# MotorPR.net
KiCad netlist of a schematic drawn in EAGLE
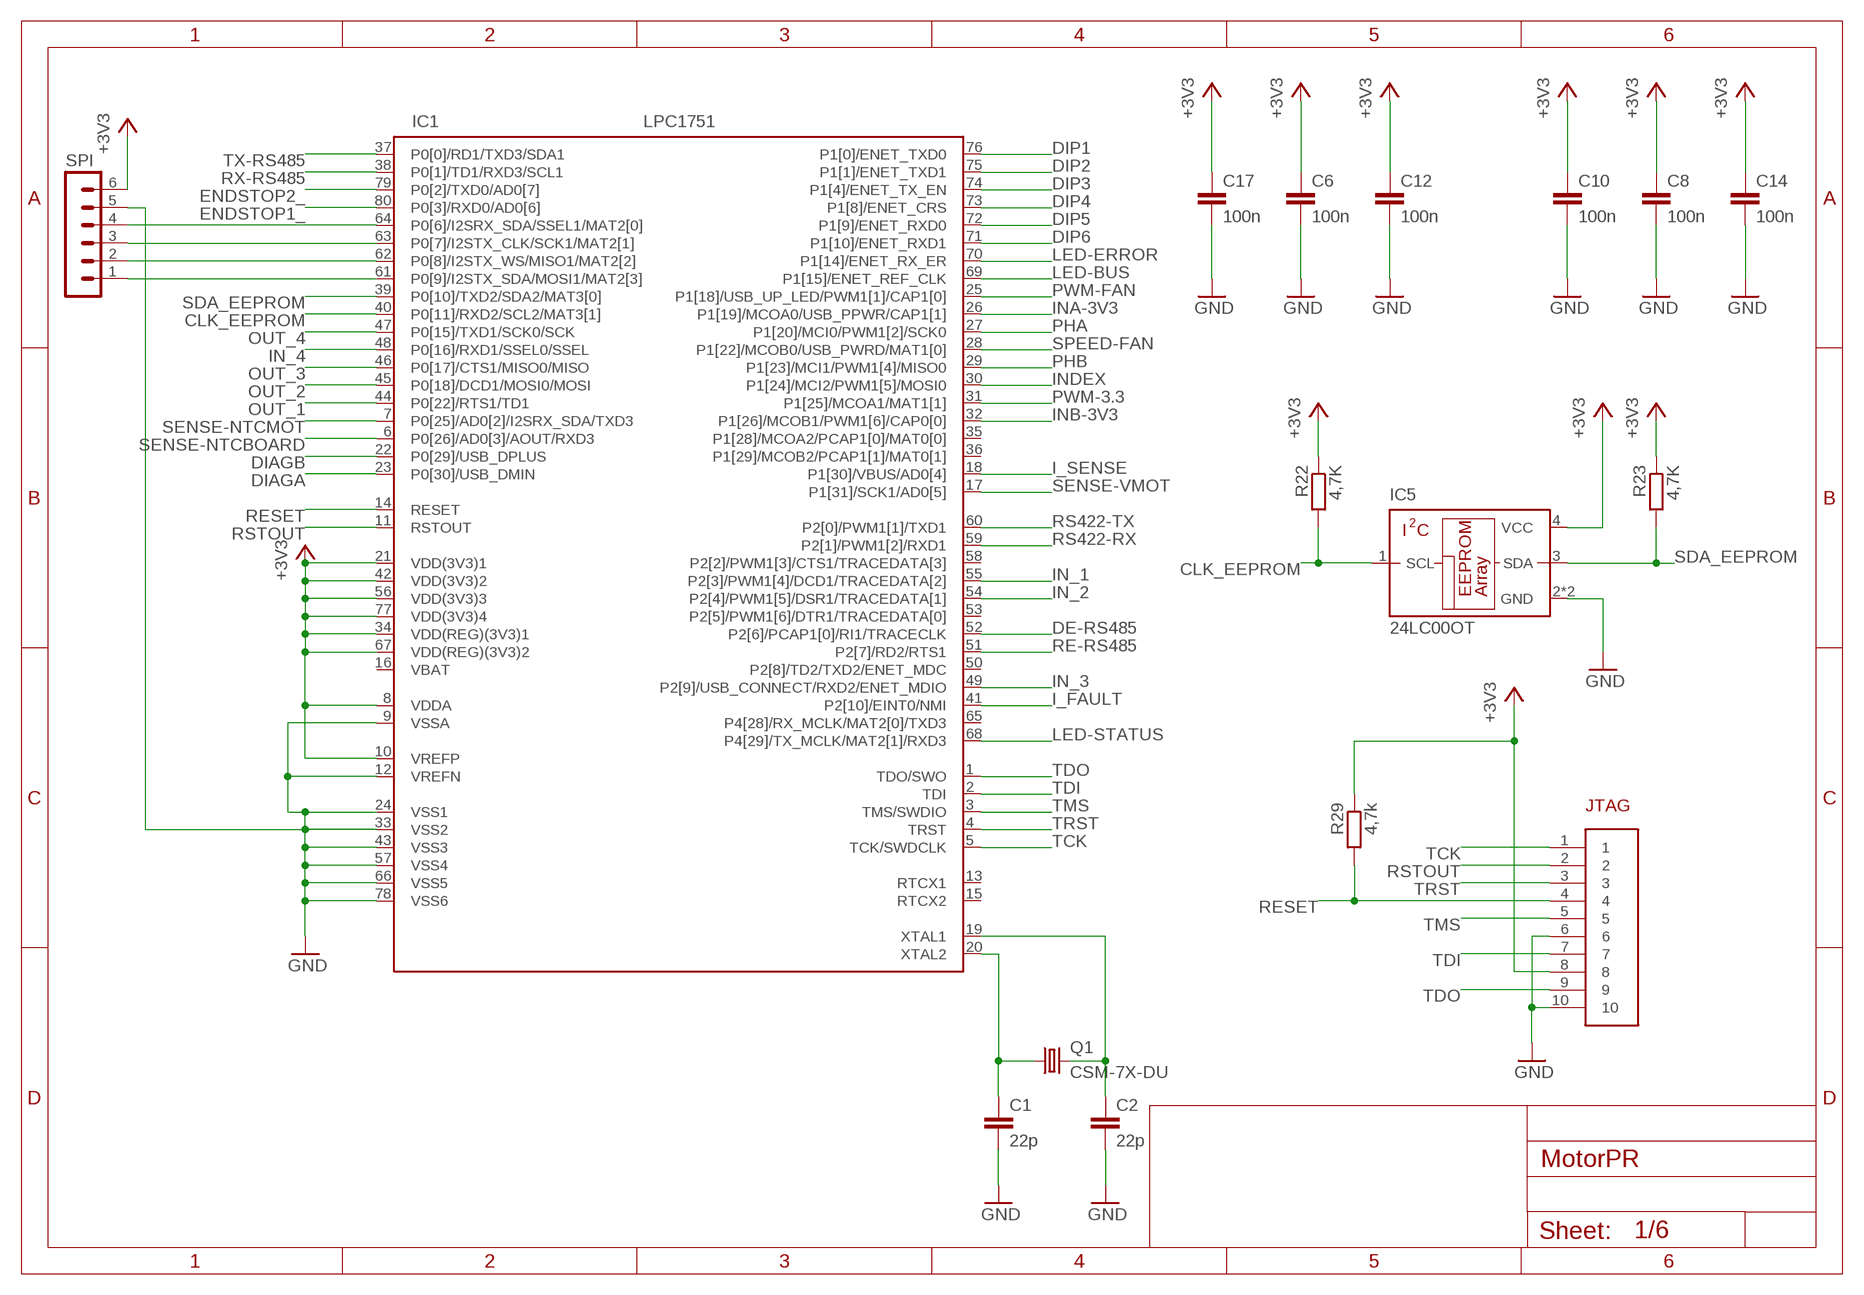
[diagram p0: schematic, sheet 1]
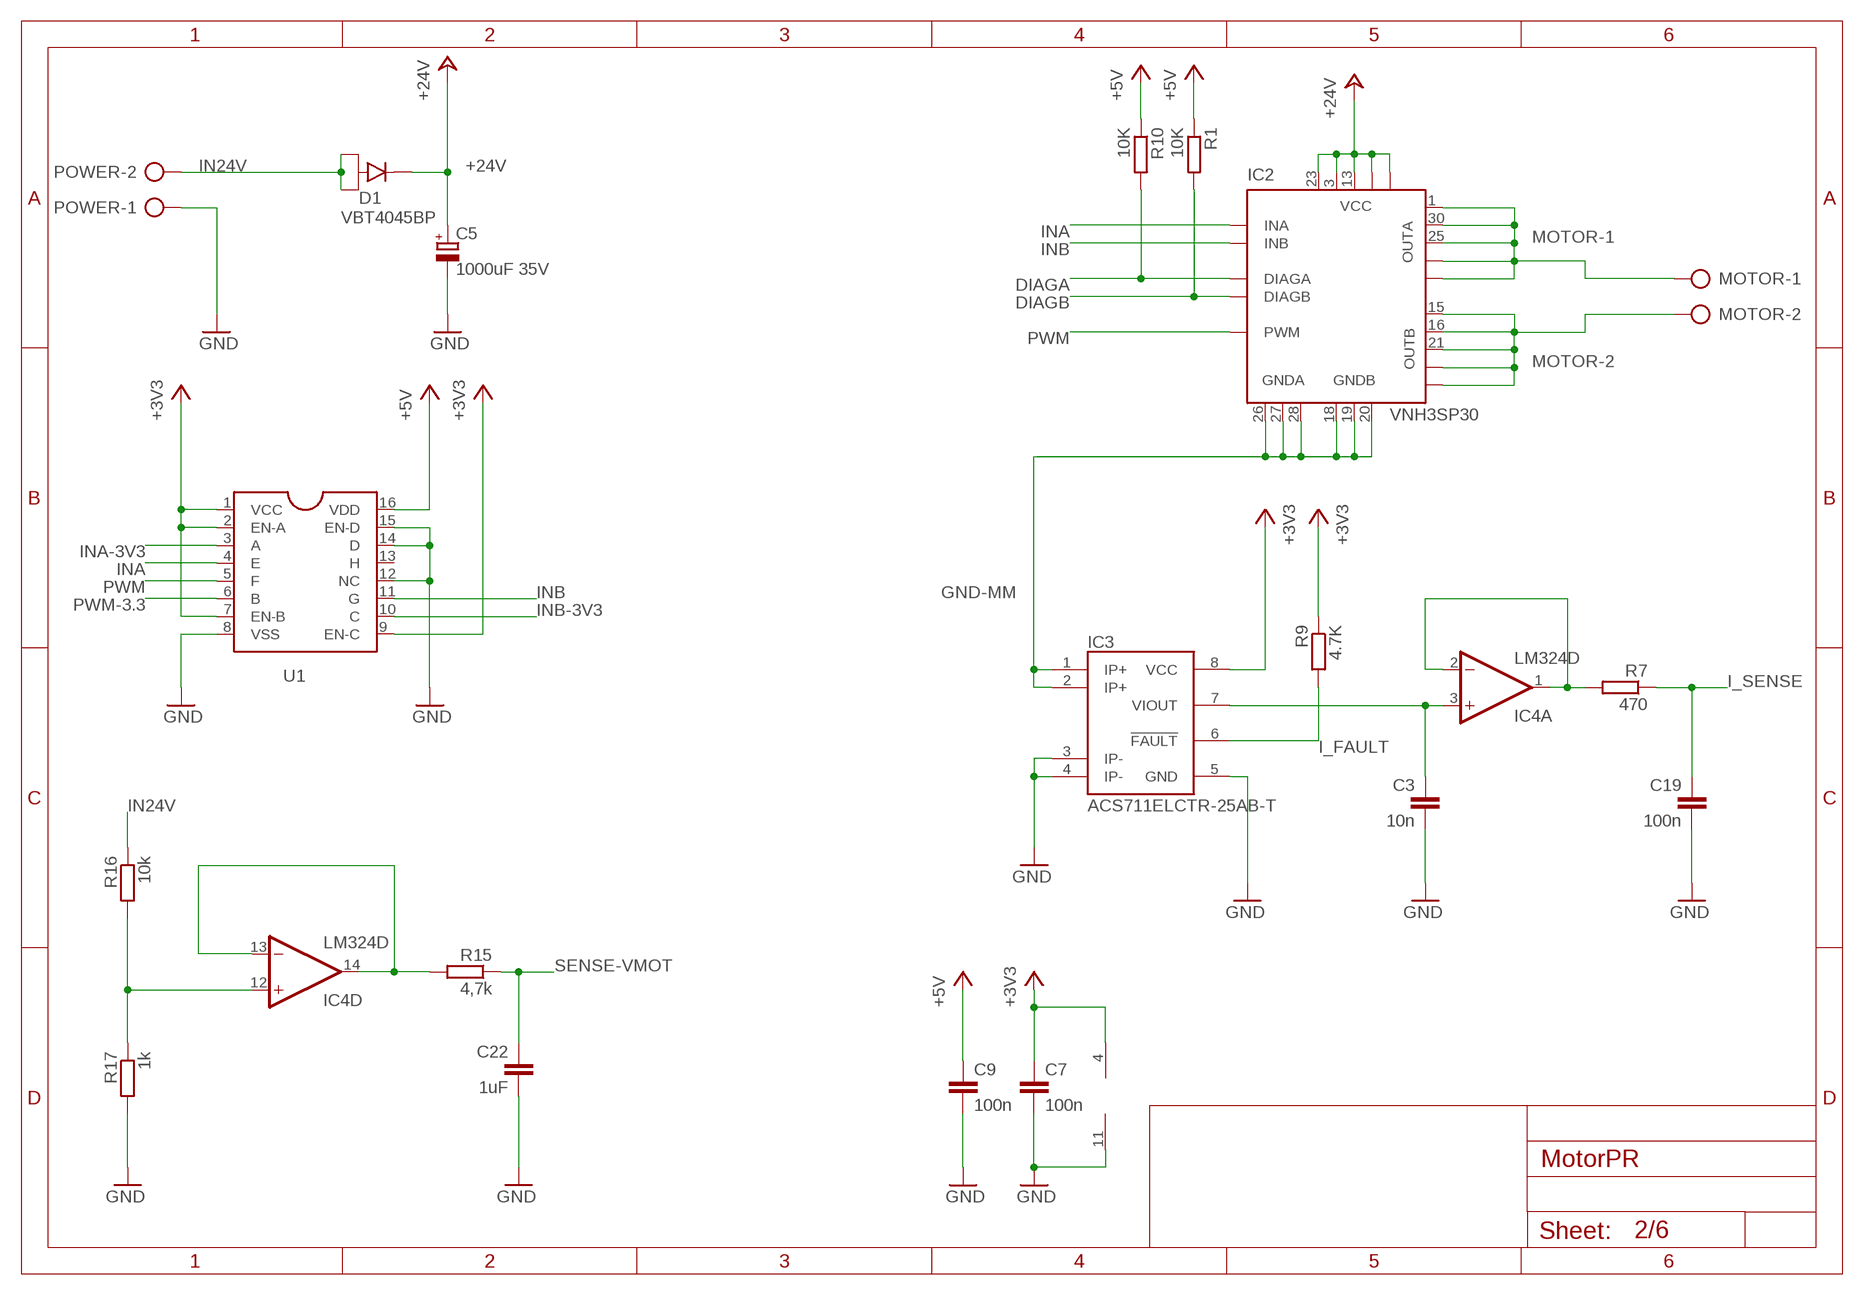
[diagram p1: schematic, sheet 2]
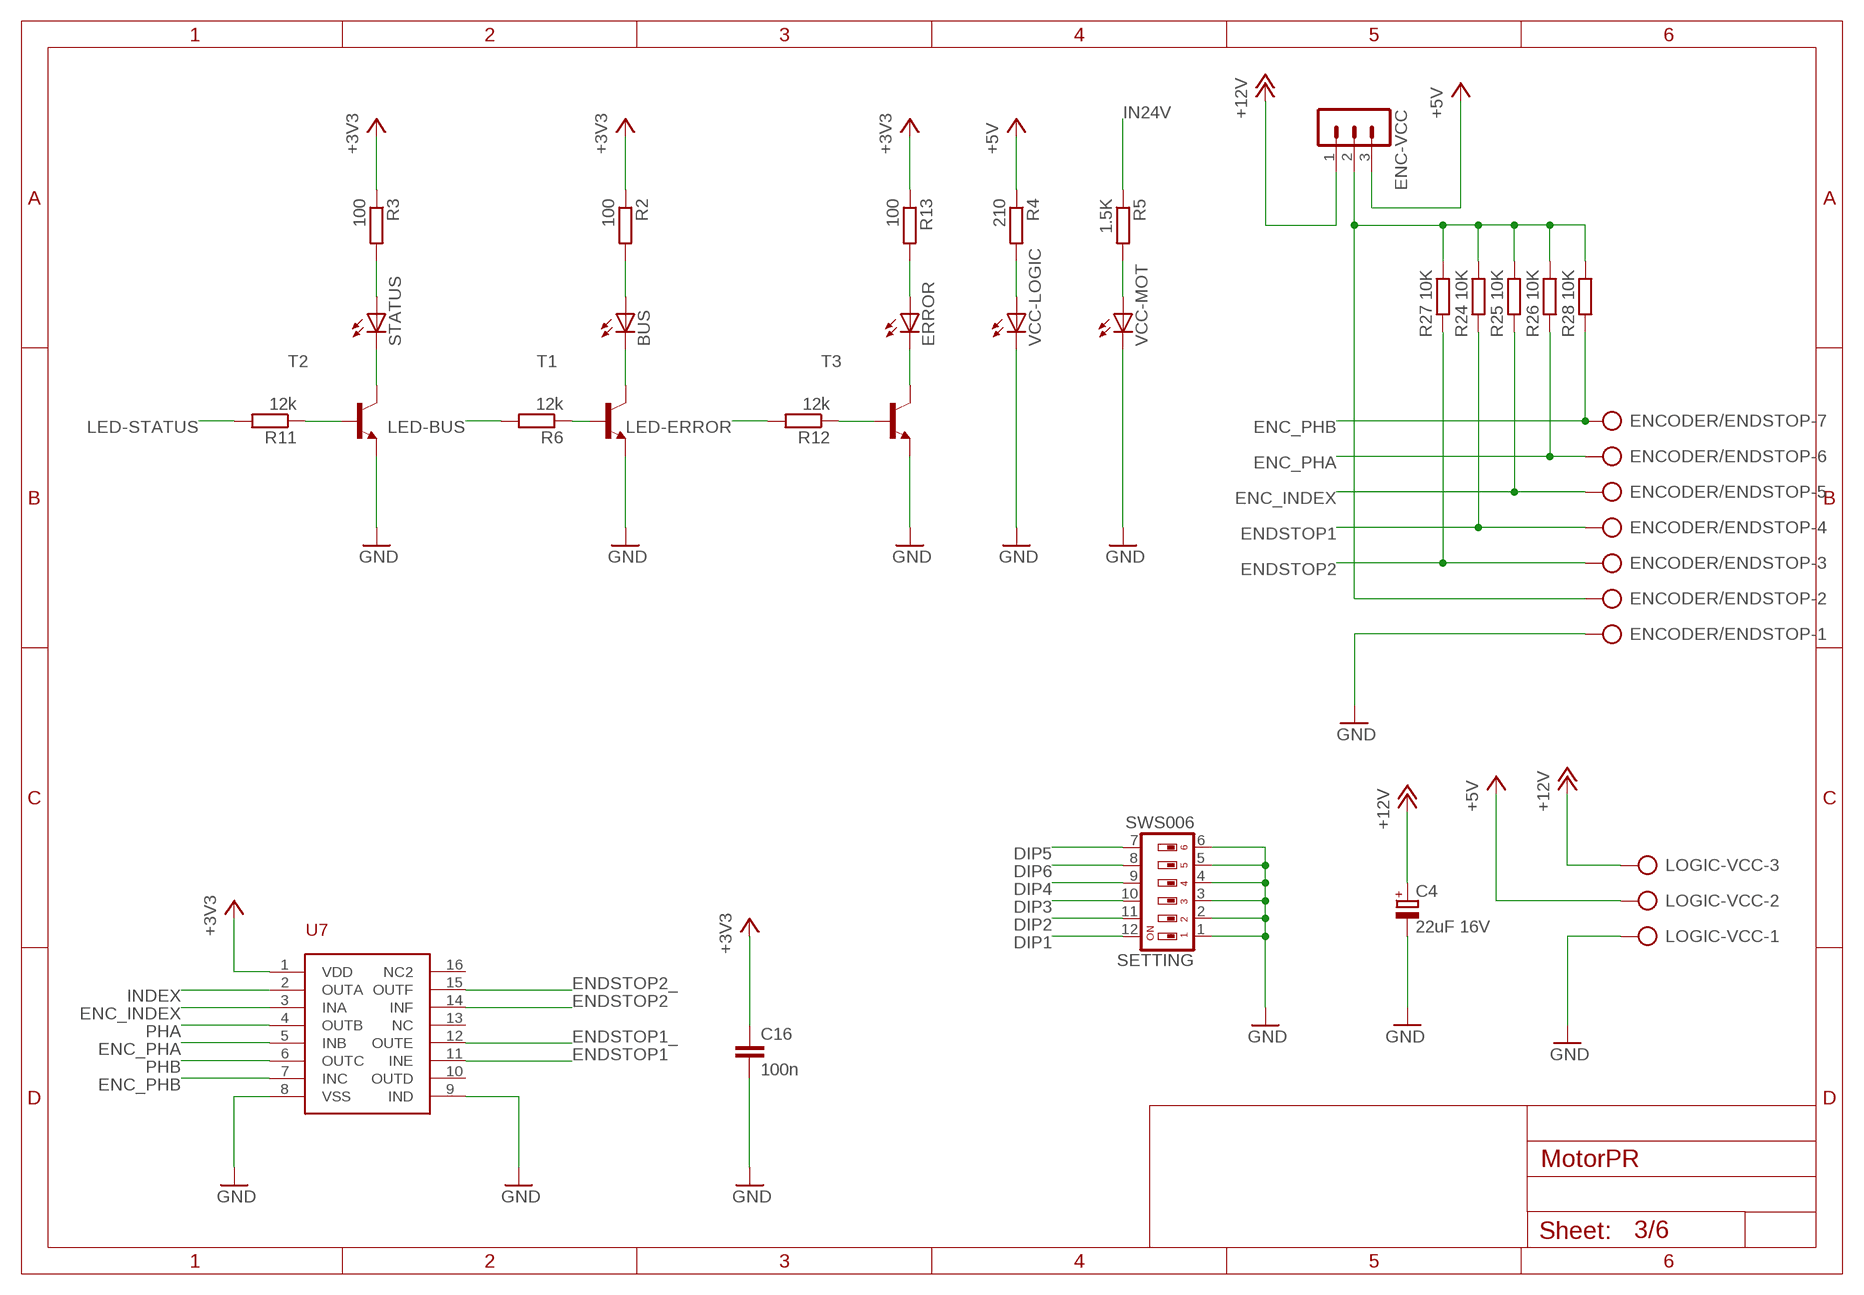
[diagram p2: schematic, sheet 3]
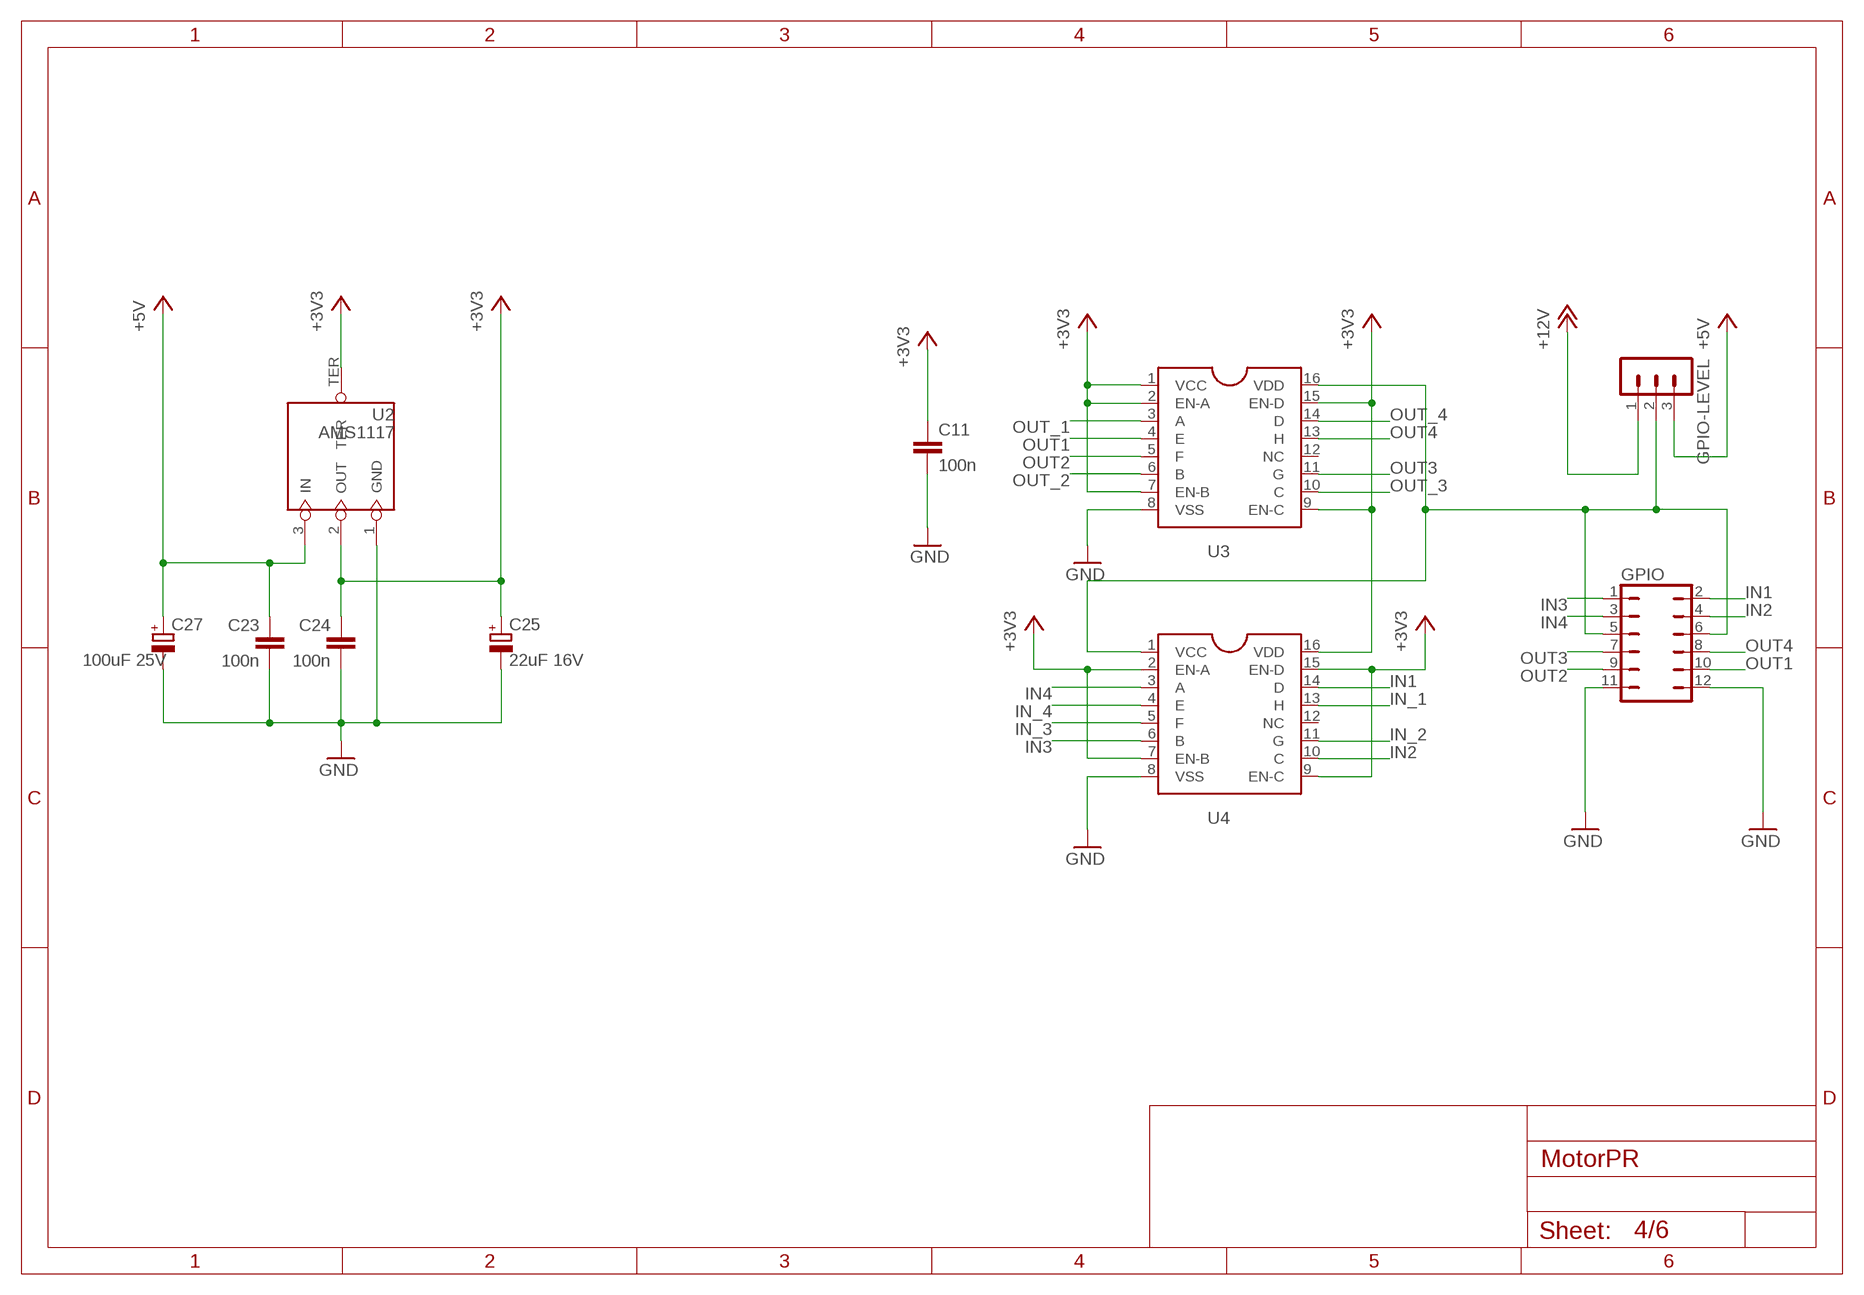
[diagram p3: schematic, sheet 4]
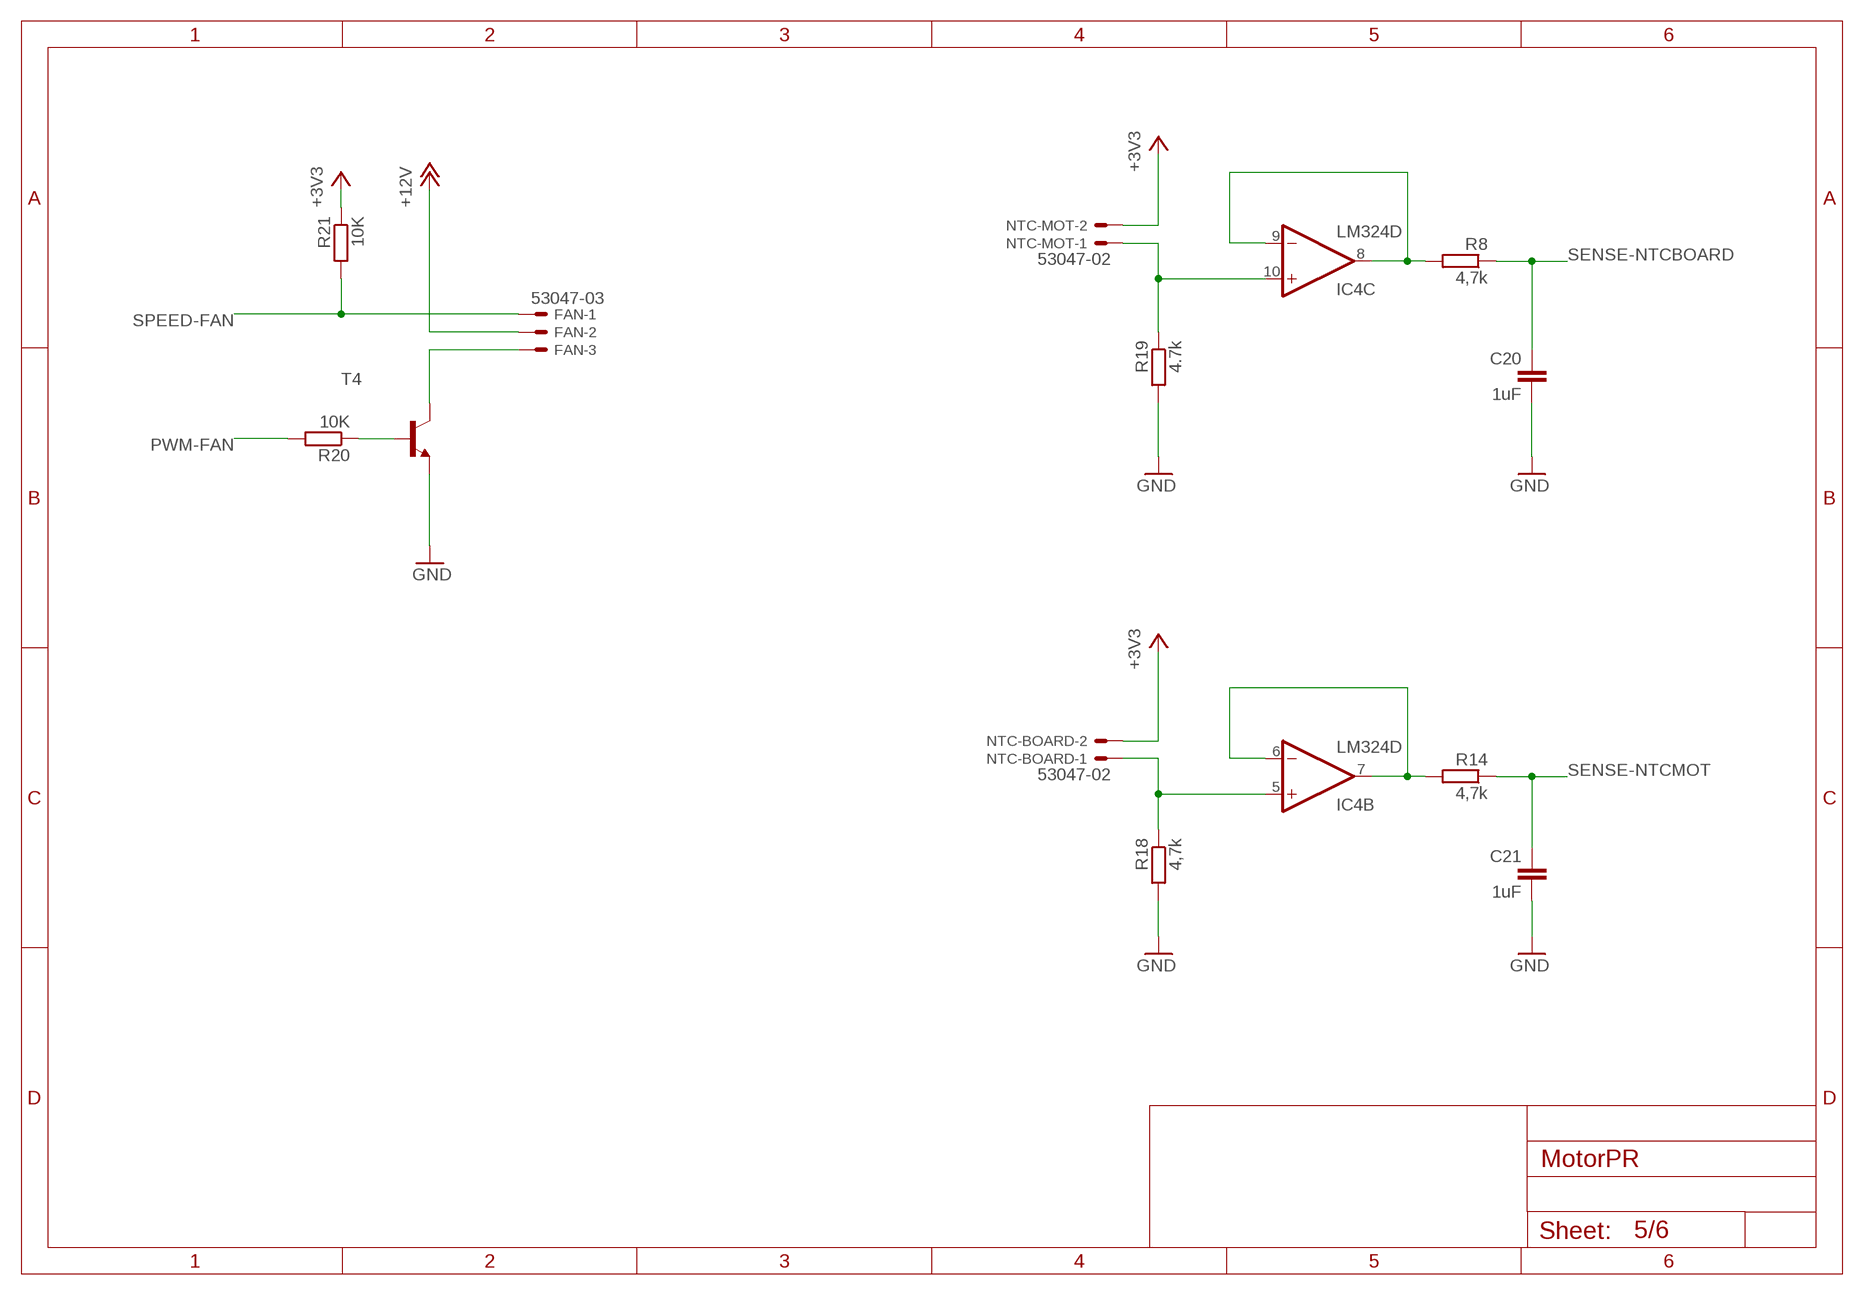
[diagram p4: schematic, sheet 5]
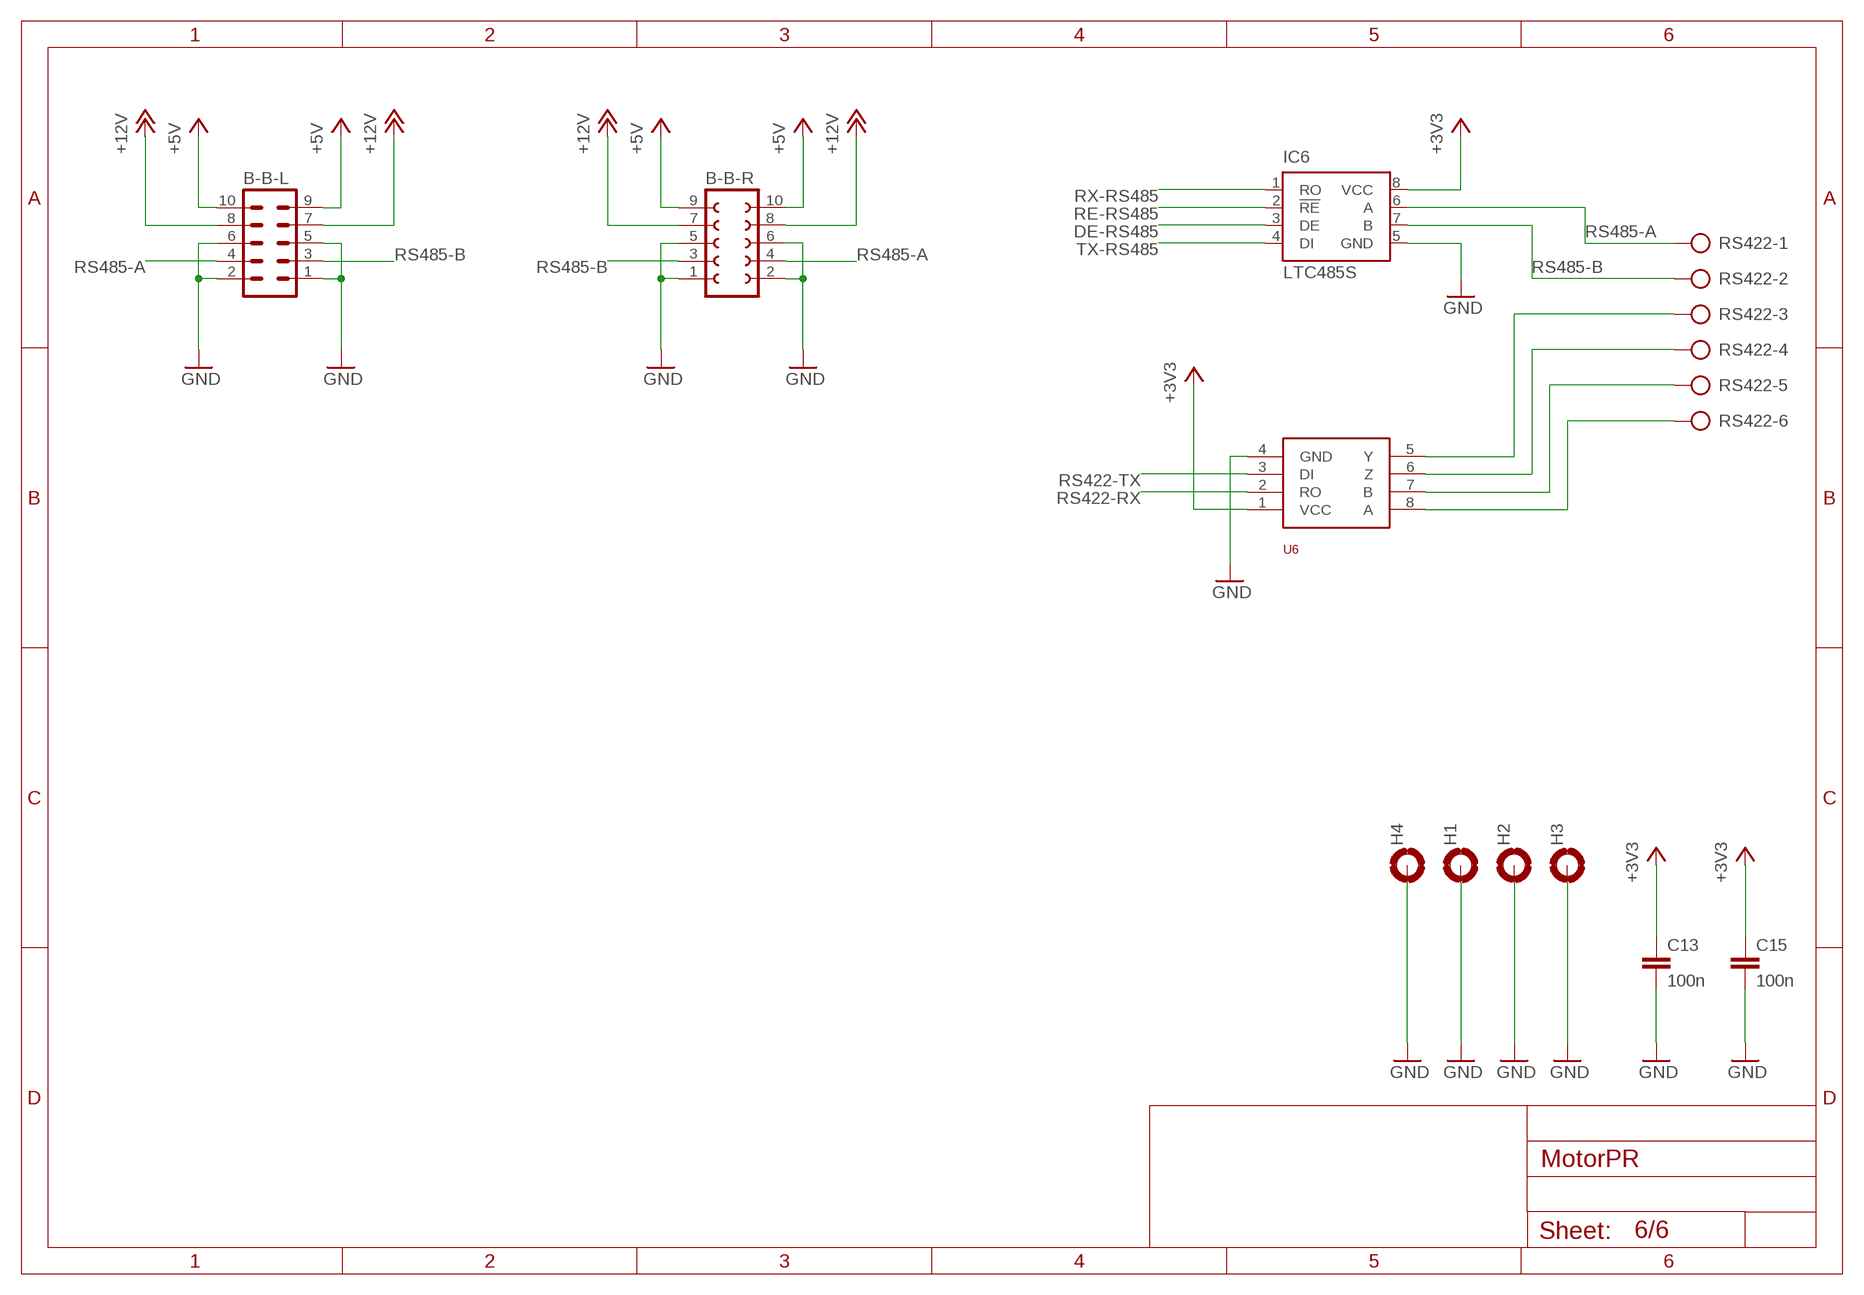
[diagram p5: schematic, sheet 6]

(export (version "E")
  (design (tool "Eeschema 10.0.6"))
  (components
    (comp (ref "C20")
      (value "1uF")
      (footprint "eagle-import:C0805")
      (libsource (lib "eagle-import") (part "C-EUC0805"))
    )
    (comp (ref "C21")
      (value "1uF")
      (footprint "eagle-import:C0805")
      (libsource (lib "eagle-import") (part "C-EUC0805"))
    )
    (comp (ref "FAN")
      (value "53047-03")
      (footprint "eagle-import:53047-03")
      (fields (field (name "MPN") "530470310"))
      (libsource (lib "eagle-import") (part "53?-03047"))
    )
    (comp (ref "IC4")
      (value "LM324D")
      (footprint "eagle-import:SO14")
      (libsource (lib "eagle-import") (part "LM324D"))
    )
    (comp (ref "NTC-BOARD")
      (value "53047-02")
      (footprint "eagle-import:53047-02")
      (fields (field (name "MF") "MOLEX") (field (name "MPN") "53047-0210"))
      (libsource (lib "eagle-import") (part "53?-02047"))
    )
    (comp (ref "NTC-MOT")
      (value "53047-02")
      (footprint "eagle-import:53047-02")
      (fields
        (field (name "MF") "MOLEX")
        (field (name "MPN") "53047-0210")
        (field (name "MF_1") "MOLEX")
        (field (name "MPN_1") "53047-0210")
        (field (name "OC_FARNELL") "9733051")
        (field (name "OC_NEWARK") "57H4701")
      )
      (libsource (lib "eagle-import") (part "53?-02047"))
    )
    (comp (ref "R8")
      (value "4,7k")
      (footprint "eagle-import:R0805W")
      (libsource (lib "eagle-import") (part "R-EU_R0805W"))
    )
    (comp (ref "R14")
      (value "4,7k")
      (footprint "eagle-import:R0805W")
      (libsource (lib "eagle-import") (part "R-EU_R0805W"))
    )
    (comp (ref "R18")
      (value "4,7k")
      (footprint "eagle-import:M1206")
      (libsource (lib "eagle-import") (part "R-EU_M1206"))
    )
    (comp (ref "R19")
      (value "4.7k")
      (footprint "eagle-import:M1206")
      (libsource (lib "eagle-import") (part "R-EU_M1206"))
    )
    (comp (ref "R20")
      (value "10K")
      (footprint "eagle-import:R0805W")
      (libsource (lib "eagle-import") (part "R-EU_R0805W"))
    )
    (comp (ref "R21")
      (value "10K")
      (footprint "eagle-import:R0805W")
      (libsource (lib "eagle-import") (part "R-EU_R0805W"))
    )
    (comp (ref "T4")
      (value "BC808-NPN-SOT23-BEC")
      (footprint "eagle-import:SOT23-BEC")
      (libsource (lib "eagle-import") (part "-NPN-SOT23-BECBC808"))
    )
    (comp (ref "C3")
      (value "10n")
      (footprint "eagle-import:C0805")
      (libsource (lib "eagle-import") (part "C-EUC0805"))
    )
    (comp (ref "C5")
      (value "1000uF 35V")
      (footprint "eagle-import:E7,5-18")
      (libsource (lib "eagle-import") (part "CPOL-EUE7.5-18"))
    )
    (comp (ref "C7")
      (value "100n")
      (footprint "eagle-import:C0805")
      (libsource (lib "eagle-import") (part "C-EUC0805"))
    )
    (comp (ref "C9")
      (value "100n")
      (footprint "eagle-import:C0805")
      (libsource (lib "eagle-import") (part "C-EUC0805"))
    )
    (comp (ref "C19")
      (value "100n")
      (footprint "eagle-import:C0805")
      (libsource (lib "eagle-import") (part "C-EUC0805"))
    )
    (comp (ref "C22")
      (value "1uF")
      (footprint "eagle-import:C0805")
      (libsource (lib "eagle-import") (part "C-EUC0805"))
    )
    (comp (ref "D1")
      (value "VBT4045BP")
      (footprint "eagle-import:TO-263AB")
      (libsource (lib "eagle-import") (part "VBT4045BP"))
    )
    (comp (ref "IC2")
      (value "VNH3SP30")
      (footprint "eagle-import:MULTIPOWERSO-30")
      (fields (field (name "MPN") "VNH3SP30-E"))
      (libsource (lib "eagle-import") (part "VNH3SP30"))
    )
    (comp (ref "IC3")
      (value "ACS711ELCTR-25AB-T")
      (footprint "eagle-import:SO08")
      (libsource (lib "eagle-import") (part "ACS711ELCTR-25AB-T"))
    )
    (comp (ref "MOTOR")
      (value "AK300/2")
      (footprint "eagle-import:AK300_2")
      (libsource (lib "eagle-import") (part "AK300/2"))
    )
    (comp (ref "POWER")
      (value "AK300/2")
      (footprint "eagle-import:AK300_2")
      (libsource (lib "eagle-import") (part "AK300/2"))
    )
    (comp (ref "R1")
      (value "10K")
      (footprint "eagle-import:R0805W")
      (libsource (lib "eagle-import") (part "R-EU_R0805W"))
    )
    (comp (ref "R7")
      (value "470")
      (footprint "eagle-import:R0805W")
      (libsource (lib "eagle-import") (part "R-EU_R0805W"))
    )
    (comp (ref "R9")
      (value "4.7K")
      (footprint "eagle-import:R0805W")
      (libsource (lib "eagle-import") (part "R-EU_R0805W"))
    )
    (comp (ref "R10")
      (value "10K")
      (footprint "eagle-import:R0805W")
      (libsource (lib "eagle-import") (part "R-EU_R0805W"))
    )
    (comp (ref "R15")
      (value "4,7k")
      (footprint "eagle-import:R0805W")
      (libsource (lib "eagle-import") (part "R-EU_R0805W"))
    )
    (comp (ref "R16")
      (value "10k")
      (footprint "eagle-import:M1206")
      (libsource (lib "eagle-import") (part "R-EU_M1206"))
    )
    (comp (ref "R17")
      (value "1k")
      (footprint "eagle-import:M1206")
      (libsource (lib "eagle-import") (part "R-EU_M1206"))
    )
    (comp (ref "U1")
      (value "CD40109B")
      (footprint "eagle-import:PW-PDSO-G16")
      (libsource (lib "eagle-import") (part "CD40109B"))
    )
    (comp (ref "BUS")
      (value "LEDCHIPLED_1206")
      (footprint "eagle-import:CHIPLED_1206")
      (libsource (lib "eagle-import") (part "LEDCHIPLED_1206"))
    )
    (comp (ref "C4")
      (value "22uF 16V")
      (footprint "eagle-import:153CLV-0605")
      (libsource (lib "eagle-import") (part "CPOL-EU153CLV-0605"))
    )
    (comp (ref "C16")
      (value "100n")
      (footprint "eagle-import:C0805")
      (libsource (lib "eagle-import") (part "C-EUC0805"))
    )
    (comp (ref "ENC-VCC")
      (value "MA03-1")
      (footprint "eagle-import:MA03-1")
      (libsource (lib "eagle-import") (part "MA03-1"))
    )
    (comp (ref "ENCODER/ENDSTOP")
      (value "AK300/7")
      (footprint "eagle-import:AK300_7")
      (libsource (lib "eagle-import") (part "AK300/7"))
    )
    (comp (ref "ERROR")
      (value "LEDCHIPLED_1206")
      (footprint "eagle-import:CHIPLED_1206")
      (libsource (lib "eagle-import") (part "LEDCHIPLED_1206"))
    )
    (comp (ref "LOGIC-VCC")
      (value "AK300/3")
      (footprint "eagle-import:AK300_3")
      (libsource (lib "eagle-import") (part "AK300/3"))
    )
    (comp (ref "R2")
      (value "100")
      (footprint "eagle-import:R0805W")
      (libsource (lib "eagle-import") (part "R-EU_R0805W"))
    )
    (comp (ref "R3")
      (value "100")
      (footprint "eagle-import:R0805W")
      (libsource (lib "eagle-import") (part "R-EU_R0805W"))
    )
    (comp (ref "R4")
      (value "210")
      (footprint "eagle-import:R0805W")
      (libsource (lib "eagle-import") (part "R-EU_R0805W"))
    )
    (comp (ref "R5")
      (value "1.5K")
      (footprint "eagle-import:R0805W")
      (libsource (lib "eagle-import") (part "R-EU_R0805W"))
    )
    (comp (ref "R6")
      (value "12k")
      (footprint "eagle-import:R0805W")
      (libsource (lib "eagle-import") (part "R-EU_R0805W"))
    )
    (comp (ref "R11")
      (value "12k")
      (footprint "eagle-import:R0805W")
      (libsource (lib "eagle-import") (part "R-EU_R0805W"))
    )
    (comp (ref "R12")
      (value "12k")
      (footprint "eagle-import:R0805W")
      (libsource (lib "eagle-import") (part "R-EU_R0805W"))
    )
    (comp (ref "R13")
      (value "100")
      (footprint "eagle-import:R0805W")
      (libsource (lib "eagle-import") (part "R-EU_R0805W"))
    )
    (comp (ref "R24")
      (value "10K")
      (footprint "eagle-import:R0805W")
      (libsource (lib "eagle-import") (part "R-EU_R0805W"))
    )
    (comp (ref "R25")
      (value "10K")
      (footprint "eagle-import:R0805W")
      (libsource (lib "eagle-import") (part "R-EU_R0805W"))
    )
    (comp (ref "R26")
      (value "10K")
      (footprint "eagle-import:R0805W")
      (libsource (lib "eagle-import") (part "R-EU_R0805W"))
    )
    (comp (ref "R27")
      (value "10K")
      (footprint "eagle-import:R0805W")
      (libsource (lib "eagle-import") (part "R-EU_R0805W"))
    )
    (comp (ref "R28")
      (value "10K")
      (footprint "eagle-import:R0805W")
      (libsource (lib "eagle-import") (part "R-EU_R0805W"))
    )
    (comp (ref "SETTING")
      (value "SWS006")
      (footprint "eagle-import:DIP6-SMD")
      (libsource (lib "eagle-import") (part "SWS006"))
    )
    (comp (ref "STATUS")
      (value "LEDCHIPLED_1206")
      (footprint "eagle-import:CHIPLED_1206")
      (libsource (lib "eagle-import") (part "LEDCHIPLED_1206"))
    )
    (comp (ref "T1")
      (value "BC808-NPN-SOT23-BEC")
      (footprint "eagle-import:SOT23-BEC")
      (libsource (lib "eagle-import") (part "-NPN-SOT23-BECBC808"))
    )
    (comp (ref "T2")
      (value "BC808-NPN-SOT23-BEC")
      (footprint "eagle-import:SOT23-BEC")
      (libsource (lib "eagle-import") (part "-NPN-SOT23-BECBC808"))
    )
    (comp (ref "T3")
      (value "BC808-NPN-SOT23-BEC")
      (footprint "eagle-import:SOT23-BEC")
      (libsource (lib "eagle-import") (part "-NPN-SOT23-BECBC808"))
    )
    (comp (ref "U7")
      (value "MC14050B")
      (footprint "eagle-import:PDSO-G16")
      (libsource (lib "eagle-import") (part "MC14050B"))
    )
    (comp (ref "VCC-LOGIC")
      (value "LEDCHIPLED_1206")
      (footprint "eagle-import:CHIPLED_1206")
      (libsource (lib "eagle-import") (part "LEDCHIPLED_1206"))
    )
    (comp (ref "VCC-MOT")
      (value "LEDCHIPLED_1206")
      (footprint "eagle-import:CHIPLED_1206")
      (libsource (lib "eagle-import") (part "LEDCHIPLED_1206"))
    )
    (comp (ref "B-B-L")
      (value "MA05-2")
      (footprint "eagle-import:MA05-2")
      (libsource (lib "eagle-import") (part "MA05-2"))
    )
    (comp (ref "B-B-R")
      (value "FE05-2W")
      (footprint "eagle-import:FE05-2W")
      (libsource (lib "eagle-import") (part "FE05-2W"))
    )
    (comp (ref "C13")
      (value "100n")
      (footprint "eagle-import:C0805")
      (libsource (lib "eagle-import") (part "C-EUC0805"))
    )
    (comp (ref "C15")
      (value "100n")
      (footprint "eagle-import:C0805")
      (libsource (lib "eagle-import") (part "C-EUC0805"))
    )
    (comp (ref "H1")
      (value "MOUNT-PAD-ROUND3.0")
      (footprint "eagle-import:3,0-PAD")
      (libsource (lib "eagle-import") (part "MOUNT-PAD-ROUND3.0"))
    )
    (comp (ref "H2")
      (value "MOUNT-PAD-ROUND3.0")
      (footprint "eagle-import:3,0-PAD")
      (libsource (lib "eagle-import") (part "MOUNT-PAD-ROUND3.0"))
    )
    (comp (ref "H3")
      (value "MOUNT-PAD-ROUND3.0")
      (footprint "eagle-import:3,0-PAD")
      (libsource (lib "eagle-import") (part "MOUNT-PAD-ROUND3.0"))
    )
    (comp (ref "H4")
      (value "MOUNT-PAD-ROUND3.0")
      (footprint "eagle-import:3,0-PAD")
      (libsource (lib "eagle-import") (part "MOUNT-PAD-ROUND3.0"))
    )
    (comp (ref "IC6")
      (value "LTC485S")
      (footprint "eagle-import:SOIC8")
      (libsource (lib "eagle-import") (part "LTC485S"))
    )
    (comp (ref "RS422")
      (value "AK300/6")
      (footprint "eagle-import:AK300_6")
      (libsource (lib "eagle-import") (part "AK300/6"))
    )
    (comp (ref "U6")
      (value "ISL83490IBZ")
      (footprint "eagle-import:R-PDSO-G8")
      (libsource (lib "eagle-import") (part "ISL83490IBZ"))
    )
    (comp (ref "C1")
      (value "22p")
      (footprint "eagle-import:C0805")
      (libsource (lib "eagle-import") (part "C-EUC0805"))
    )
    (comp (ref "C2")
      (value "22p")
      (footprint "eagle-import:C0805")
      (libsource (lib "eagle-import") (part "C-EUC0805"))
    )
    (comp (ref "C6")
      (value "100n")
      (footprint "eagle-import:C0805")
      (libsource (lib "eagle-import") (part "C-EUC0805"))
    )
    (comp (ref "C8")
      (value "100n")
      (footprint "eagle-import:C0805")
      (libsource (lib "eagle-import") (part "C-EUC0805"))
    )
    (comp (ref "C10")
      (value "100n")
      (footprint "eagle-import:C0805")
      (libsource (lib "eagle-import") (part "C-EUC0805"))
    )
    (comp (ref "C12")
      (value "100n")
      (footprint "eagle-import:C0805")
      (libsource (lib "eagle-import") (part "C-EUC0805"))
    )
    (comp (ref "C14")
      (value "100n")
      (footprint "eagle-import:C0805")
      (libsource (lib "eagle-import") (part "C-EUC0805"))
    )
    (comp (ref "C17")
      (value "100n")
      (footprint "eagle-import:C0805")
      (libsource (lib "eagle-import") (part "C-EUC0805"))
    )
    (comp (ref "IC1")
      (value "LPC1751")
      (footprint "eagle-import:LQFP80-12X12")
      (libsource (lib "eagle-import") (part "LPC1751"))
    )
    (comp (ref "IC5")
      (value "24LC00OT")
      (footprint "eagle-import:SOT23-5L")
      (fields (field (name "MF") "MICROCHIP") (field (name "MPN") "24LC00T-I/OT"))
      (libsource (lib "eagle-import") (part "2400OTLC"))
    )
    (comp (ref "JTAG")
      (value "MOLEX-52808-1070")
      (footprint "eagle-import:MOLEX-52808-1070")
      (libsource (lib "eagle-import") (part "MOLEX-52808-1070"))
    )
    (comp (ref "Q1")
      (value "CSM-7X-DU")
      (footprint "eagle-import:CSM-7X-DU")
      (libsource (lib "eagle-import") (part "CSM-7X-DU"))
    )
    (comp (ref "R22")
      (value "4,7K")
      (footprint "eagle-import:R0805W")
      (libsource (lib "eagle-import") (part "R-EU_R0805W"))
    )
    (comp (ref "R23")
      (value "4,7K")
      (footprint "eagle-import:R0805W")
      (libsource (lib "eagle-import") (part "R-EU_R0805W"))
    )
    (comp (ref "R29")
      (value "4,7k")
      (footprint "eagle-import:R0805W")
      (libsource (lib "eagle-import") (part "R-EU_R0805W"))
    )
    (comp (ref "SPI")
      (value "MA06-1")
      (footprint "eagle-import:MA06-1")
      (libsource (lib "eagle-import") (part "MA06-1"))
    )
    (comp (ref "C11")
      (value "100n")
      (footprint "eagle-import:C0805")
      (libsource (lib "eagle-import") (part "C-EUC0805"))
    )
    (comp (ref "C23")
      (value "100n")
      (footprint "eagle-import:C0805")
      (libsource (lib "eagle-import") (part "C-EUC0805"))
    )
    (comp (ref "C24")
      (value "100n")
      (footprint "eagle-import:C0805")
      (libsource (lib "eagle-import") (part "C-EUC0805"))
    )
    (comp (ref "C25")
      (value "22uF 16V")
      (footprint "eagle-import:153CLV-0605")
      (libsource (lib "eagle-import") (part "CPOL-EU153CLV-0605"))
    )
    (comp (ref "C27")
      (value "100uF 25V")
      (footprint "eagle-import:153CLV-0807")
      (libsource (lib "eagle-import") (part "CPOL-EU153CLV-0807"))
    )
    (comp (ref "GPIO")
      (value "JP6Q")
      (footprint "eagle-import:JP6Q")
      (libsource (lib "eagle-import") (part "JP6Q"))
    )
    (comp (ref "GPIO-LEVEL")
      (value "MA03-1")
      (footprint "eagle-import:MA03-1")
      (libsource (lib "eagle-import") (part "MA03-1"))
    )
    (comp (ref "U2")
      (value "AMS1117")
      (footprint "eagle-import:SOT-223")
      (libsource (lib "eagle-import") (part "AMS1117"))
    )
    (comp (ref "U3")
      (value "CD40109B")
      (footprint "eagle-import:PW-PDSO-G16")
      (libsource (lib "eagle-import") (part "CD40109B"))
    )
    (comp (ref "U4")
      (value "CD40109B")
      (footprint "eagle-import:PW-PDSO-G16")
      (libsource (lib "eagle-import") (part "CD40109B"))
    )
  )
  (nets
    (net (code "1") (name "+3V3") (class "Default")
      (node (ref "C10") (pin "1") (pinfunction "1_1") (pintype "passive"))
      (node (ref "C11") (pin "1") (pinfunction "1_1") (pintype "passive"))
      (node (ref "C12") (pin "1") (pinfunction "1_1") (pintype "passive"))
      (node (ref "C13") (pin "1") (pinfunction "1_1") (pintype "passive"))
      (node (ref "C14") (pin "1") (pinfunction "1_1") (pintype "passive"))
      (node (ref "C15") (pin "1") (pinfunction "1_1") (pintype "passive"))
      (node (ref "C16") (pin "1") (pinfunction "1_1") (pintype "passive"))
      (node (ref "C17") (pin "1") (pinfunction "1_1") (pintype "passive"))
      (node (ref "C24") (pin "1") (pinfunction "1_1") (pintype "passive"))
      (node (ref "C25") (pin "+") (pinfunction "+_+") (pintype "passive"))
      (node (ref "C6") (pin "1") (pinfunction "1_1") (pintype "passive"))
      (node (ref "C7") (pin "1") (pinfunction "1_1") (pintype "passive"))
      (node (ref "C8") (pin "1") (pinfunction "1_1") (pintype "passive"))
      (node (ref "IC1") (pin "10") (pinfunction "VREFP_10") (pintype "input"))
      (node (ref "IC1") (pin "21") (pinfunction "VDD(3V3)1_21") (pintype "power_in"))
      (node (ref "IC1") (pin "34") (pinfunction "VDD(REG)(3V3)1_34") (pintype "power_in"))
      (node (ref "IC1") (pin "42") (pinfunction "VDD(3V3)2_42") (pintype "power_in"))
      (node (ref "IC1") (pin "56") (pinfunction "VDD(3V3)3_56") (pintype "power_in"))
      (node (ref "IC1") (pin "67") (pinfunction "VDD(REG)(3V3)2_67") (pintype "power_in"))
      (node (ref "IC1") (pin "77") (pinfunction "VDD(3V3)4_77") (pintype "power_in"))
      (node (ref "IC1") (pin "8") (pinfunction "VDDA_8") (pintype "power_in"))
      (node (ref "IC3") (pin "8") (pinfunction "VCC_8") (pintype "power_in"))
      (node (ref "IC4") (pin "4") (pinfunction "V+_4") (pintype "power_in"))
      (node (ref "IC5") (pin "4") (pinfunction "VCC_4") (pintype "power_in"))
      (node (ref "IC6") (pin "8") (pinfunction "VCC_8") (pintype "input"))
      (node (ref "JTAG") (pin "8") (pinfunction "8_8") (pintype "bidirectional"))
      (node (ref "NTC-BOARD") (pin "2") (pinfunction "S_2") (pintype "passive"))
      (node (ref "NTC-MOT") (pin "2") (pinfunction "S_2") (pintype "passive"))
      (node (ref "R13") (pin "1") (pinfunction "1_1") (pintype "passive"))
      (node (ref "R2") (pin "1") (pinfunction "1_1") (pintype "passive"))
      (node (ref "R21") (pin "1") (pinfunction "1_1") (pintype "passive"))
      (node (ref "R22") (pin "1") (pinfunction "1_1") (pintype "passive"))
      (node (ref "R23") (pin "1") (pinfunction "1_1") (pintype "passive"))
      (node (ref "R29") (pin "1") (pinfunction "1_1") (pintype "passive"))
      (node (ref "R3") (pin "1") (pinfunction "1_1") (pintype "passive"))
      (node (ref "R9") (pin "1") (pinfunction "1_1") (pintype "passive"))
      (node (ref "SPI") (pin "6") (pinfunction "6_6") (pintype "passive"))
      (node (ref "U1") (pin "1") (pinfunction "VCC_1") (pintype "bidirectional"))
      (node (ref "U1") (pin "2") (pinfunction "EN-A_2") (pintype "bidirectional"))
      (node (ref "U1") (pin "7") (pinfunction "EN-B_7") (pintype "bidirectional"))
      (node (ref "U1") (pin "9") (pinfunction "EN-C_9") (pintype "bidirectional"))
      (node (ref "U2") (pin "2") (pinfunction "OUT_2") (pintype "bidirectional"))
      (node (ref "U2") (pin "TER") (pinfunction "TER_TER") (pintype "bidirectional"))
      (node (ref "U3") (pin "1") (pinfunction "VCC_1") (pintype "bidirectional"))
      (node (ref "U3") (pin "15") (pinfunction "EN-D_15") (pintype "bidirectional"))
      (node (ref "U3") (pin "2") (pinfunction "EN-A_2") (pintype "bidirectional"))
      (node (ref "U3") (pin "7") (pinfunction "EN-B_7") (pintype "bidirectional"))
      (node (ref "U3") (pin "9") (pinfunction "EN-C_9") (pintype "bidirectional"))
      (node (ref "U4") (pin "15") (pinfunction "EN-D_15") (pintype "bidirectional"))
      (node (ref "U4") (pin "16") (pinfunction "VDD_16") (pintype "bidirectional"))
      (node (ref "U4") (pin "2") (pinfunction "EN-A_2") (pintype "bidirectional"))
      (node (ref "U4") (pin "7") (pinfunction "EN-B_7") (pintype "bidirectional"))
      (node (ref "U4") (pin "9") (pinfunction "EN-C_9") (pintype "bidirectional"))
      (node (ref "U6") (pin "1") (pinfunction "VCC_1") (pintype "bidirectional"))
      (node (ref "U7") (pin "1") (pinfunction "VDD_1") (pintype "bidirectional"))
    )
    (net (code "2") (name "+5V") (class "Default")
      (node (ref "B-B-L") (pin "10") (pinfunction "10_10") (pintype "passive"))
      (node (ref "B-B-L") (pin "9") (pinfunction "9_9") (pintype "passive"))
      (node (ref "B-B-R") (pin "10") (pinfunction "10_10") (pintype "passive"))
      (node (ref "B-B-R") (pin "9") (pinfunction "9_9") (pintype "passive"))
      (node (ref "C23") (pin "1") (pinfunction "1_1") (pintype "passive"))
      (node (ref "C27") (pin "+") (pinfunction "+_+") (pintype "passive"))
      (node (ref "C9") (pin "1") (pinfunction "1_1") (pintype "passive"))
      (node (ref "ENC-VCC") (pin "3") (pinfunction "3_3") (pintype "passive"))
      (node (ref "GPIO-LEVEL") (pin "3") (pinfunction "3_3") (pintype "passive"))
      (node (ref "LOGIC-VCC") (pin "2") (pinfunction "KL_2") (pintype "passive"))
      (node (ref "R1") (pin "1") (pinfunction "1_1") (pintype "passive"))
      (node (ref "R10") (pin "1") (pinfunction "1_1") (pintype "passive"))
      (node (ref "R4") (pin "1") (pinfunction "1_1") (pintype "passive"))
      (node (ref "U1") (pin "16") (pinfunction "VDD_16") (pintype "bidirectional"))
      (node (ref "U2") (pin "3") (pinfunction "IN_3") (pintype "bidirectional"))
    )
    (net (code "3") (name "+12V") (class "Default")
      (node (ref "B-B-L") (pin "7") (pinfunction "7_7") (pintype "passive"))
      (node (ref "B-B-L") (pin "8") (pinfunction "8_8") (pintype "passive"))
      (node (ref "B-B-R") (pin "7") (pinfunction "7_7") (pintype "passive"))
      (node (ref "B-B-R") (pin "8") (pinfunction "8_8") (pintype "passive"))
      (node (ref "C4") (pin "+") (pinfunction "+_+") (pintype "passive"))
      (node (ref "ENC-VCC") (pin "1") (pinfunction "1_1") (pintype "passive"))
      (node (ref "FAN") (pin "2") (pinfunction "S_2") (pintype "passive"))
      (node (ref "GPIO-LEVEL") (pin "1") (pinfunction "1_1") (pintype "passive"))
      (node (ref "LOGIC-VCC") (pin "3") (pinfunction "KL_3") (pintype "passive"))
    )
    (net (code "4") (name "+24V") (class "Default")
      (node (ref "C5") (pin "+") (pinfunction "+_+") (pintype "passive"))
      (node (ref "D1") (pin "K") (pinfunction "K_K") (pintype "output"))
      (node (ref "IC2") (pin "13") (pinfunction "VCC_13") (pintype "power_in"))
      (node (ref "IC2") (pin "23") (pinfunction "VCC_23") (pintype "power_in"))
      (node (ref "IC2") (pin "3") (pinfunction "VCC_3") (pintype "power_in"))
      (node (ref "IC2") (pin "VCC") (pinfunction "VCC_VCC") (pintype "power_in"))
      (node (ref "IC2") (pin "VCC@1") (pinfunction "VCC_VCC@1") (pintype "power_in"))
    )
    (net (code "5") (name "CLK_EEPROM") (class "Default")
      (node (ref "IC1") (pin "40") (pinfunction "P0[11]/RXD2/SCL2/MAT3[1]_40") (pintype "bidirectional"))
      (node (ref "IC5") (pin "1") (pinfunction "SCL_1") (pintype "input"))
      (node (ref "R22") (pin "2") (pinfunction "2_2") (pintype "passive"))
    )
    (net (code "6") (name "DE-RS485") (class "Default")
      (node (ref "IC1") (pin "52") (pinfunction "P2[6]/PCAP1[0]/RI1/TRACECLK_52") (pintype "bidirectional"))
      (node (ref "IC6") (pin "3") (pinfunction "DE_3") (pintype "input"))
    )
    (net (code "7") (name "DIAGA") (class "Default")
      (node (ref "IC1") (pin "23") (pinfunction "P0[30]/USB_DMIN_23") (pintype "bidirectional"))
      (node (ref "IC2") (pin "6") (pinfunction "DIAGA_6") (pintype "open_collector"))
      (node (ref "R10") (pin "2") (pinfunction "2_2") (pintype "passive"))
    )
    (net (code "8") (name "DIAGB") (class "Default")
      (node (ref "IC1") (pin "22") (pinfunction "P0[29]/USB_DPLUS_22") (pintype "bidirectional"))
      (node (ref "IC2") (pin "10") (pinfunction "DIAGB_10") (pintype "open_collector"))
      (node (ref "R1") (pin "2") (pinfunction "2_2") (pintype "passive"))
    )
    (net (code "9") (name "DIP1") (class "Default")
      (node (ref "IC1") (pin "76") (pinfunction "P1[0]/ENET_TXD0_76") (pintype "bidirectional"))
      (node (ref "SETTING") (pin "12") (pinfunction "12_12") (pintype "passive"))
    )
    (net (code "10") (name "DIP2") (class "Default")
      (node (ref "IC1") (pin "75") (pinfunction "P1[1]/ENET_TXD1_75") (pintype "bidirectional"))
      (node (ref "SETTING") (pin "11") (pinfunction "11_11") (pintype "passive"))
    )
    (net (code "11") (name "DIP3") (class "Default")
      (node (ref "IC1") (pin "74") (pinfunction "P1[4]/ENET_TX_EN_74") (pintype "bidirectional"))
      (node (ref "SETTING") (pin "10") (pinfunction "10_10") (pintype "passive"))
    )
    (net (code "12") (name "DIP4") (class "Default")
      (node (ref "IC1") (pin "73") (pinfunction "P1[8]/ENET_CRS_73") (pintype "bidirectional"))
      (node (ref "SETTING") (pin "9") (pinfunction "9_9") (pintype "passive"))
    )
    (net (code "13") (name "DIP5") (class "Default")
      (node (ref "IC1") (pin "72") (pinfunction "P1[9]/ENET_RXD0_72") (pintype "bidirectional"))
      (node (ref "SETTING") (pin "7") (pinfunction "7_7") (pintype "passive"))
    )
    (net (code "14") (name "DIP6") (class "Default")
      (node (ref "IC1") (pin "71") (pinfunction "P1[10]/ENET_RXD1_71") (pintype "bidirectional"))
      (node (ref "SETTING") (pin "8") (pinfunction "8_8") (pintype "passive"))
    )
    (net (code "15") (name "ENC_INDEX") (class "Default")
      (node (ref "ENCODER/ENDSTOP") (pin "5") (pinfunction "KL_5") (pintype "passive"))
      (node (ref "R25") (pin "2") (pinfunction "2_2") (pintype "passive"))
      (node (ref "U7") (pin "3") (pinfunction "INA_3") (pintype "bidirectional"))
    )
    (net (code "16") (name "ENC_PHA") (class "Default")
      (node (ref "ENCODER/ENDSTOP") (pin "6") (pinfunction "KL_6") (pintype "passive"))
      (node (ref "R26") (pin "2") (pinfunction "2_2") (pintype "passive"))
      (node (ref "U7") (pin "5") (pinfunction "INB_5") (pintype "bidirectional"))
    )
    (net (code "17") (name "ENC_PHB") (class "Default")
      (node (ref "ENCODER/ENDSTOP") (pin "7") (pinfunction "KL_7") (pintype "passive"))
      (node (ref "R28") (pin "2") (pinfunction "2_2") (pintype "passive"))
      (node (ref "U7") (pin "7") (pinfunction "INC_7") (pintype "bidirectional"))
    )
    (net (code "18") (name "ENDSTOP1") (class "Default")
      (node (ref "ENCODER/ENDSTOP") (pin "4") (pinfunction "KL_4") (pintype "passive"))
      (node (ref "R24") (pin "2") (pinfunction "2_2") (pintype "passive"))
      (node (ref "U7") (pin "11") (pinfunction "INE_11") (pintype "bidirectional"))
    )
    (net (code "19") (name "ENDSTOP1_") (class "Default")
      (node (ref "IC1") (pin "80") (pinfunction "P0[3]/RXD0/AD0[6]_80") (pintype "bidirectional"))
      (node (ref "U7") (pin "12") (pinfunction "OUTE_12") (pintype "bidirectional"))
    )
    (net (code "20") (name "ENDSTOP2") (class "Default")
      (node (ref "ENCODER/ENDSTOP") (pin "3") (pinfunction "KL_3") (pintype "passive"))
      (node (ref "R27") (pin "2") (pinfunction "2_2") (pintype "passive"))
      (node (ref "U7") (pin "14") (pinfunction "INF_14") (pintype "bidirectional"))
    )
    (net (code "21") (name "ENDSTOP2_") (class "Default")
      (node (ref "IC1") (pin "79") (pinfunction "P0[2]/TXD0/AD0[7]_79") (pintype "bidirectional"))
      (node (ref "U7") (pin "15") (pinfunction "OUTF_15") (pintype "bidirectional"))
    )
    (net (code "22") (name "GND") (class "Default")
      (node (ref "B-B-L") (pin "1") (pinfunction "1_1") (pintype "passive"))
      (node (ref "B-B-L") (pin "2") (pinfunction "2_2") (pintype "passive"))
      (node (ref "B-B-L") (pin "5") (pinfunction "5_5") (pintype "passive"))
      (node (ref "B-B-L") (pin "6") (pinfunction "6_6") (pintype "passive"))
      (node (ref "B-B-R") (pin "1") (pinfunction "1_1") (pintype "passive"))
      (node (ref "B-B-R") (pin "2") (pinfunction "2_2") (pintype "passive"))
      (node (ref "B-B-R") (pin "5") (pinfunction "5_5") (pintype "passive"))
      (node (ref "B-B-R") (pin "6") (pinfunction "6_6") (pintype "passive"))
      (node (ref "C1") (pin "2") (pinfunction "2_2") (pintype "passive"))
      (node (ref "C10") (pin "2") (pinfunction "2_2") (pintype "passive"))
      (node (ref "C11") (pin "2") (pinfunction "2_2") (pintype "passive"))
      (node (ref "C12") (pin "2") (pinfunction "2_2") (pintype "passive"))
      (node (ref "C13") (pin "2") (pinfunction "2_2") (pintype "passive"))
      (node (ref "C14") (pin "2") (pinfunction "2_2") (pintype "passive"))
      (node (ref "C15") (pin "2") (pinfunction "2_2") (pintype "passive"))
      (node (ref "C16") (pin "2") (pinfunction "2_2") (pintype "passive"))
      (node (ref "C17") (pin "2") (pinfunction "2_2") (pintype "passive"))
      (node (ref "C19") (pin "2") (pinfunction "2_2") (pintype "passive"))
      (node (ref "C2") (pin "2") (pinfunction "2_2") (pintype "passive"))
      (node (ref "C20") (pin "2") (pinfunction "2_2") (pintype "passive"))
      (node (ref "C21") (pin "2") (pinfunction "2_2") (pintype "passive"))
      (node (ref "C22") (pin "2") (pinfunction "2_2") (pintype "passive"))
      (node (ref "C23") (pin "2") (pinfunction "2_2") (pintype "passive"))
      (node (ref "C24") (pin "2") (pinfunction "2_2") (pintype "passive"))
      (node (ref "C25") (pin "-") (pinfunction "-_-") (pintype "passive"))
      (node (ref "C27") (pin "-") (pinfunction "-_-") (pintype "passive"))
      (node (ref "C3") (pin "2") (pinfunction "2_2") (pintype "passive"))
      (node (ref "C4") (pin "-") (pinfunction "-_-") (pintype "passive"))
      (node (ref "C5") (pin "-") (pinfunction "-_-") (pintype "passive"))
      (node (ref "C6") (pin "2") (pinfunction "2_2") (pintype "passive"))
      (node (ref "C7") (pin "2") (pinfunction "2_2") (pintype "passive"))
      (node (ref "C8") (pin "2") (pinfunction "2_2") (pintype "passive"))
      (node (ref "C9") (pin "2") (pinfunction "2_2") (pintype "passive"))
      (node (ref "ENCODER/ENDSTOP") (pin "1") (pinfunction "KL_1") (pintype "passive"))
      (node (ref "GPIO") (pin "11") (pinfunction "11_11") (pintype "passive"))
      (node (ref "GPIO") (pin "12") (pinfunction "12_12") (pintype "passive"))
      (node (ref "H1") (pin "B3,0") (pinfunction "MOUNT_B3,0") (pintype "passive"))
      (node (ref "H2") (pin "B3,0") (pinfunction "MOUNT_B3,0") (pintype "passive"))
      (node (ref "H3") (pin "B3,0") (pinfunction "MOUNT_B3,0") (pintype "passive"))
      (node (ref "H4") (pin "B3,0") (pinfunction "MOUNT_B3,0") (pintype "passive"))
      (node (ref "IC1") (pin "12") (pinfunction "VREFN_12") (pintype "input"))
      (node (ref "IC1") (pin "24") (pinfunction "VSS1_24") (pintype "power_in"))
      (node (ref "IC1") (pin "33") (pinfunction "VSS2_33") (pintype "power_in"))
      (node (ref "IC1") (pin "43") (pinfunction "VSS3_43") (pintype "power_in"))
      (node (ref "IC1") (pin "57") (pinfunction "VSS4_57") (pintype "power_in"))
      (node (ref "IC1") (pin "66") (pinfunction "VSS5_66") (pintype "power_in"))
      (node (ref "IC1") (pin "78") (pinfunction "VSS6_78") (pintype "power_in"))
      (node (ref "IC1") (pin "9") (pinfunction "VSSA_9") (pintype "power_in"))
      (node (ref "IC3") (pin "3") (pinfunction "IP-_3") (pintype "passive"))
      (node (ref "IC3") (pin "4") (pinfunction "IP-_4") (pintype "passive"))
      (node (ref "IC3") (pin "5") (pinfunction "GND_5") (pintype "power_in"))
      (node (ref "IC4") (pin "11") (pinfunction "V-_11") (pintype "power_in"))
      (node (ref "IC5") (pin "2") (pinfunction "GND_2") (pintype "power_in"))
      (node (ref "IC5") (pin "5") (pinfunction "GND_5") (pintype "power_in"))
      (node (ref "IC6") (pin "5") (pinfunction "GND_5") (pintype "input"))
      (node (ref "JTAG") (pin "10") (pinfunction "10_10") (pintype "bidirectional"))
      (node (ref "JTAG") (pin "6") (pinfunction "6_6") (pintype "bidirectional"))
      (node (ref "LOGIC-VCC") (pin "1") (pinfunction "KL_1") (pintype "passive"))
      (node (ref "POWER") (pin "1") (pinfunction "KL_1") (pintype "passive"))
      (node (ref "R17") (pin "2") (pinfunction "2_2") (pintype "passive"))
      (node (ref "R18") (pin "2") (pinfunction "2_2") (pintype "passive"))
      (node (ref "R19") (pin "2") (pinfunction "2_2") (pintype "passive"))
      (node (ref "SETTING") (pin "1") (pinfunction "1_1") (pintype "passive"))
      (node (ref "SETTING") (pin "2") (pinfunction "2_2") (pintype "passive"))
      (node (ref "SETTING") (pin "3") (pinfunction "3_3") (pintype "passive"))
      (node (ref "SETTING") (pin "4") (pinfunction "4_4") (pintype "passive"))
      (node (ref "SETTING") (pin "5") (pinfunction "5_5") (pintype "passive"))
      (node (ref "SETTING") (pin "6") (pinfunction "6_6") (pintype "passive"))
      (node (ref "SPI") (pin "5") (pinfunction "5_5") (pintype "passive"))
      (node (ref "T1") (pin "E") (pinfunction "E_E") (pintype "passive"))
      (node (ref "T2") (pin "E") (pinfunction "E_E") (pintype "passive"))
      (node (ref "T3") (pin "E") (pinfunction "E_E") (pintype "passive"))
      (node (ref "T4") (pin "E") (pinfunction "E_E") (pintype "passive"))
      (node (ref "U1") (pin "12") (pinfunction "NC_12") (pintype "bidirectional"))
      (node (ref "U1") (pin "14") (pinfunction "D_14") (pintype "bidirectional"))
      (node (ref "U1") (pin "15") (pinfunction "EN-D_15") (pintype "bidirectional"))
      (node (ref "U1") (pin "8") (pinfunction "VSS_8") (pintype "bidirectional"))
      (node (ref "U2") (pin "1") (pinfunction "GND_1") (pintype "bidirectional"))
      (node (ref "U3") (pin "8") (pinfunction "VSS_8") (pintype "bidirectional"))
      (node (ref "U4") (pin "8") (pinfunction "VSS_8") (pintype "bidirectional"))
      (node (ref "U6") (pin "4") (pinfunction "GND_4") (pintype "bidirectional"))
      (node (ref "U7") (pin "8") (pinfunction "VSS_8") (pintype "bidirectional"))
      (node (ref "U7") (pin "9") (pinfunction "IND_9") (pintype "bidirectional"))
      (node (ref "VCC-LOGIC") (pin "C") (pinfunction "C_C") (pintype "passive"))
      (node (ref "VCC-MOT") (pin "C") (pinfunction "C_C") (pintype "passive"))
    )
    (net (code "23") (name "GND-MM") (class "Default")
      (node (ref "IC2") (pin "18") (pinfunction "GNDB_18") (pintype "power_in"))
      (node (ref "IC2") (pin "19") (pinfunction "GNDB_19") (pintype "power_in"))
      (node (ref "IC2") (pin "20") (pinfunction "GNDB_20") (pintype "power_in"))
      (node (ref "IC2") (pin "26") (pinfunction "GNDA_26") (pintype "power_in"))
      (node (ref "IC2") (pin "27") (pinfunction "GNDA_27") (pintype "power_in"))
      (node (ref "IC2") (pin "28") (pinfunction "GNDA_28") (pintype "power_in"))
      (node (ref "IC3") (pin "1") (pinfunction "IP+_1") (pintype "passive"))
      (node (ref "IC3") (pin "2") (pinfunction "IP+_2") (pintype "passive"))
    )
    (net (code "24") (name "IN1") (class "Default")
      (node (ref "GPIO") (pin "2") (pinfunction "2_2") (pintype "passive"))
      (node (ref "U4") (pin "14") (pinfunction "D_14") (pintype "bidirectional"))
    )
    (net (code "25") (name "IN2") (class "Default")
      (node (ref "GPIO") (pin "4") (pinfunction "4_4") (pintype "passive"))
      (node (ref "U4") (pin "10") (pinfunction "C_10") (pintype "bidirectional"))
    )
    (net (code "26") (name "IN3") (class "Default")
      (node (ref "GPIO") (pin "1") (pinfunction "1_1") (pintype "passive"))
      (node (ref "U4") (pin "6") (pinfunction "B_6") (pintype "bidirectional"))
    )
    (net (code "27") (name "IN4") (class "Default")
      (node (ref "GPIO") (pin "3") (pinfunction "3_3") (pintype "passive"))
      (node (ref "U4") (pin "3") (pinfunction "A_3") (pintype "bidirectional"))
    )
    (net (code "28") (name "IN24V") (class "Default")
      (node (ref "D1") (pin "A1") (pinfunction "A1_A1") (pintype "input"))
      (node (ref "D1") (pin "A2") (pinfunction "A2_A2") (pintype "input"))
      (node (ref "POWER") (pin "2") (pinfunction "KL_2") (pintype "passive"))
      (node (ref "R16") (pin "1") (pinfunction "1_1") (pintype "passive"))
      (node (ref "R5") (pin "1") (pinfunction "1_1") (pintype "passive"))
    )
    (net (code "29") (name "INA") (class "Default")
      (node (ref "IC2") (pin "5") (pinfunction "INA_5") (pintype "input"))
      (node (ref "U1") (pin "4") (pinfunction "E_4") (pintype "bidirectional"))
    )
    (net (code "30") (name "INA-3V3") (class "Default")
      (node (ref "IC1") (pin "26") (pinfunction "P1[19]/MCOA0/USB_PPWR/CAP1[1]_26") (pintype "bidirectional"))
      (node (ref "U1") (pin "3") (pinfunction "A_3") (pintype "bidirectional"))
    )
    (net (code "31") (name "INB") (class "Default")
      (node (ref "IC2") (pin "11") (pinfunction "INB_11") (pintype "input"))
      (node (ref "U1") (pin "11") (pinfunction "G_11") (pintype "bidirectional"))
    )
    (net (code "32") (name "INB-3V3") (class "Default")
      (node (ref "IC1") (pin "32") (pinfunction "P1[26]/MCOB1/PWM1[6]/CAP0[0]_32") (pintype "bidirectional"))
      (node (ref "U1") (pin "10") (pinfunction "C_10") (pintype "bidirectional"))
    )
    (net (code "33") (name "INDEX") (class "Default")
      (node (ref "IC1") (pin "30") (pinfunction "P1[24]/MCI2/PWM1[5]/MOSI0_30") (pintype "bidirectional"))
      (node (ref "U7") (pin "2") (pinfunction "OUTA_2") (pintype "bidirectional"))
    )
    (net (code "34") (name "IN_1") (class "Default")
      (node (ref "IC1") (pin "55") (pinfunction "P2[3]/PWM1[4]/DCD1/TRACEDATA[2]_55") (pintype "bidirectional"))
      (node (ref "U4") (pin "13") (pinfunction "H_13") (pintype "bidirectional"))
    )
    (net (code "35") (name "IN_2") (class "Default")
      (node (ref "IC1") (pin "54") (pinfunction "P2[4]/PWM1[5]/DSR1/TRACEDATA[1]_54") (pintype "bidirectional"))
      (node (ref "U4") (pin "11") (pinfunction "G_11") (pintype "bidirectional"))
    )
    (net (code "36") (name "IN_3") (class "Default")
      (node (ref "IC1") (pin "49") (pinfunction "P2[9]/USB_CONNECT/RXD2/ENET_MDIO_49") (pintype "bidirectional"))
      (node (ref "U4") (pin "5") (pinfunction "F_5") (pintype "bidirectional"))
    )
    (net (code "37") (name "IN_4") (class "Default")
      (node (ref "IC1") (pin "48") (pinfunction "P0[16]/RXD1/SSEL0/SSEL_48") (pintype "bidirectional"))
      (node (ref "U4") (pin "4") (pinfunction "E_4") (pintype "bidirectional"))
    )
    (net (code "38") (name "I_FAULT") (class "Default")
      (node (ref "IC1") (pin "41") (pinfunction "P2[10]/EINT0/NMI_41") (pintype "bidirectional"))
      (node (ref "IC3") (pin "6") (pinfunction "~{FAULT}_6") (pintype "output"))
      (node (ref "R9") (pin "2") (pinfunction "2_2") (pintype "passive"))
    )
    (net (code "39") (name "I_SENSE") (class "Default")
      (node (ref "C19") (pin "1") (pinfunction "1_1") (pintype "passive"))
      (node (ref "IC1") (pin "18") (pinfunction "P1[30]/VBUS/AD0[4]_18") (pintype "bidirectional"))
      (node (ref "R7") (pin "1") (pinfunction "1_1") (pintype "passive"))
    )
    (net (code "40") (name "LED-BUS") (class "Default")
      (node (ref "IC1") (pin "69") (pinfunction "P1[15]/ENET_REF_CLK_69") (pintype "bidirectional"))
      (node (ref "R6") (pin "2") (pinfunction "2_2") (pintype "passive"))
    )
    (net (code "41") (name "LED-ERROR") (class "Default")
      (node (ref "IC1") (pin "70") (pinfunction "P1[14]/ENET_RX_ER_70") (pintype "bidirectional"))
      (node (ref "R12") (pin "2") (pinfunction "2_2") (pintype "passive"))
    )
    (net (code "42") (name "LED-STATUS") (class "Default")
      (node (ref "IC1") (pin "68") (pinfunction "P4[29]/TX_MCLK/MAT2[1]/RXD3_68") (pintype "bidirectional"))
      (node (ref "R11") (pin "2") (pinfunction "2_2") (pintype "passive"))
    )
    (net (code "43") (name "MOTOR-1") (class "Default")
      (node (ref "IC2") (pin "1") (pinfunction "OUTA_1") (pintype "output"))
      (node (ref "IC2") (pin "25") (pinfunction "OUTA_25") (pintype "passive"))
      (node (ref "IC2") (pin "30") (pinfunction "OUTA_30") (pintype "passive"))
      (node (ref "IC2") (pin "OUTA") (pinfunction "OUTA_OUTA") (pintype "passive"))
      (node (ref "IC2") (pin "OUTA@1") (pinfunction "OUTA_OUTA@1") (pintype "passive"))
      (node (ref "MOTOR") (pin "1") (pinfunction "KL_1") (pintype "passive"))
    )
    (net (code "44") (name "MOTOR-2") (class "Default")
      (node (ref "IC2") (pin "15") (pinfunction "OUTB_15") (pintype "output"))
      (node (ref "IC2") (pin "16") (pinfunction "OUTB_16") (pintype "passive"))
      (node (ref "IC2") (pin "21") (pinfunction "OUTB_21") (pintype "passive"))
      (node (ref "IC2") (pin "OUTB") (pinfunction "OUTB_OUTB") (pintype "passive"))
      (node (ref "IC2") (pin "OUTB@1") (pinfunction "OUTB_OUTB@1") (pintype "passive"))
      (node (ref "MOTOR") (pin "2") (pinfunction "KL_2") (pintype "passive"))
    )
    (net (code "45") (name "Net-(BUS-PadA)") (class "Default")
      (node (ref "BUS") (pin "A") (pinfunction "A_A") (pintype "passive"))
      (node (ref "R2") (pin "2") (pinfunction "2_2") (pintype "passive"))
    )
    (net (code "46") (name "Net-(BUS-PadC)") (class "Default")
      (node (ref "BUS") (pin "C") (pinfunction "C_C") (pintype "passive"))
      (node (ref "T1") (pin "C") (pinfunction "C_C") (pintype "passive"))
    )
    (net (code "47") (name "Net-(ENCODER/ENDSTOPB-KL)") (class "Default")
      (node (ref "ENC-VCC") (pin "2") (pinfunction "2_2") (pintype "passive"))
      (node (ref "ENCODER/ENDSTOP") (pin "2") (pinfunction "KL_2") (pintype "passive"))
      (node (ref "R24") (pin "1") (pinfunction "1_1") (pintype "passive"))
      (node (ref "R25") (pin "1") (pinfunction "1_1") (pintype "passive"))
      (node (ref "R26") (pin "1") (pinfunction "1_1") (pintype "passive"))
      (node (ref "R27") (pin "1") (pinfunction "1_1") (pintype "passive"))
      (node (ref "R28") (pin "1") (pinfunction "1_1") (pintype "passive"))
    )
    (net (code "48") (name "Net-(ERROR-PadA)") (class "Default")
      (node (ref "ERROR") (pin "A") (pinfunction "A_A") (pintype "passive"))
      (node (ref "R13") (pin "2") (pinfunction "2_2") (pintype "passive"))
    )
    (net (code "49") (name "Net-(ERROR-PadC)") (class "Default")
      (node (ref "ERROR") (pin "C") (pinfunction "C_C") (pintype "passive"))
      (node (ref "T3") (pin "C") (pinfunction "C_C") (pintype "passive"))
    )
    (net (code "50") (name "Net-(FANC-S)") (class "Default")
      (node (ref "FAN") (pin "3") (pinfunction "S_3") (pintype "passive"))
      (node (ref "T4") (pin "C") (pinfunction "C_C") (pintype "passive"))
    )
    (net (code "51") (name "Net-(IC1-P0[6]{slash}I2SRX_SDA{slash}SSEL1{slash}MAT2[0])") (class "Default")
      (node (ref "IC1") (pin "64") (pinfunction "P0[6]/I2SRX_SDA/SSEL1/MAT2[0]_64") (pintype "bidirectional"))
      (node (ref "SPI") (pin "4") (pinfunction "4_4") (pintype "passive"))
    )
    (net (code "52") (name "Net-(IC1-P0[7]{slash}I2STX_CLK{slash}SCK1{slash}MAT2[1])") (class "Default")
      (node (ref "IC1") (pin "63") (pinfunction "P0[7]/I2STX_CLK/SCK1/MAT2[1]_63") (pintype "bidirectional"))
      (node (ref "SPI") (pin "3") (pinfunction "3_3") (pintype "passive"))
    )
    (net (code "53") (name "Net-(IC1-P0[8]{slash}I2STX_WS{slash}MISO1{slash}MAT2[2])") (class "Default")
      (node (ref "IC1") (pin "62") (pinfunction "P0[8]/I2STX_WS/MISO1/MAT2[2]_62") (pintype "bidirectional"))
      (node (ref "SPI") (pin "2") (pinfunction "2_2") (pintype "passive"))
    )
    (net (code "54") (name "Net-(IC1-P0[9]{slash}I2STX_SDA{slash}MOSI1{slash}MAT2[3])") (class "Default")
      (node (ref "IC1") (pin "61") (pinfunction "P0[9]/I2STX_SDA/MOSI1/MAT2[3]_61") (pintype "bidirectional"))
      (node (ref "SPI") (pin "1") (pinfunction "1_1") (pintype "passive"))
    )
    (net (code "55") (name "Net-(IC1-XTAL1)") (class "Default")
      (node (ref "C2") (pin "1") (pinfunction "1_1") (pintype "passive"))
      (node (ref "IC1") (pin "19") (pinfunction "XTAL1_19") (pintype "input"))
      (node (ref "Q1") (pin "2") (pinfunction "2_2") (pintype "passive"))
    )
    (net (code "56") (name "Net-(IC1-XTAL2)") (class "Default")
      (node (ref "C1") (pin "1") (pinfunction "1_1") (pintype "passive"))
      (node (ref "IC1") (pin "20") (pinfunction "XTAL2_20") (pintype "output"))
      (node (ref "Q1") (pin "1") (pinfunction "1_1") (pintype "passive"))
    )
    (net (code "57") (name "Net-(IC3-VIOUT)") (class "Default")
      (node (ref "C3") (pin "1") (pinfunction "1_1") (pintype "passive"))
      (node (ref "IC3") (pin "7") (pinfunction "VIOUT_7") (pintype "output"))
      (node (ref "IC4") (pin "3") (pinfunction "+IN_3") (pintype "input"))
    )
    (net (code "58") (name "Net-(IC4A--IN)") (class "Default")
      (node (ref "IC4") (pin "1") (pinfunction "OUT_1") (pintype "output"))
      (node (ref "IC4") (pin "2") (pinfunction "-IN_2") (pintype "input"))
      (node (ref "R7") (pin "2") (pinfunction "2_2") (pintype "passive"))
    )
    (net (code "59") (name "Net-(IC4B-+IN)") (class "Default")
      (node (ref "IC4") (pin "5") (pinfunction "+IN_5") (pintype "input"))
      (node (ref "NTC-BOARD") (pin "1") (pinfunction "S_1") (pintype "passive"))
      (node (ref "R18") (pin "1") (pinfunction "1_1") (pintype "passive"))
    )
    (net (code "60") (name "Net-(IC4B--IN)") (class "Default")
      (node (ref "IC4") (pin "6") (pinfunction "-IN_6") (pintype "input"))
      (node (ref "IC4") (pin "7") (pinfunction "OUT_7") (pintype "output"))
      (node (ref "R14") (pin "2") (pinfunction "2_2") (pintype "passive"))
    )
    (net (code "61") (name "Net-(IC4C-+IN)") (class "Default")
      (node (ref "IC4") (pin "10") (pinfunction "+IN_10") (pintype "input"))
      (node (ref "NTC-MOT") (pin "1") (pinfunction "S_1") (pintype "passive"))
      (node (ref "R19") (pin "1") (pinfunction "1_1") (pintype "passive"))
    )
    (net (code "62") (name "Net-(IC4C--IN)") (class "Default")
      (node (ref "IC4") (pin "8") (pinfunction "OUT_8") (pintype "output"))
      (node (ref "IC4") (pin "9") (pinfunction "-IN_9") (pintype "input"))
      (node (ref "R8") (pin "2") (pinfunction "2_2") (pintype "passive"))
    )
    (net (code "63") (name "Net-(IC4D-+IN)") (class "Default")
      (node (ref "IC4") (pin "12") (pinfunction "+IN_12") (pintype "input"))
      (node (ref "R16") (pin "2") (pinfunction "2_2") (pintype "passive"))
      (node (ref "R17") (pin "1") (pinfunction "1_1") (pintype "passive"))
    )
    (net (code "64") (name "Net-(IC4D--IN)") (class "Default")
      (node (ref "IC4") (pin "13") (pinfunction "-IN_13") (pintype "input"))
      (node (ref "IC4") (pin "14") (pinfunction "OUT_14") (pintype "output"))
      (node (ref "R15") (pin "2") (pinfunction "2_2") (pintype "passive"))
    )
    (net (code "65") (name "Net-(R3-Pad2)") (class "Default")
      (node (ref "R3") (pin "2") (pinfunction "2_2") (pintype "passive"))
      (node (ref "STATUS") (pin "A") (pinfunction "A_A") (pintype "passive"))
    )
    (net (code "66") (name "Net-(R4-Pad2)") (class "Default")
      (node (ref "R4") (pin "2") (pinfunction "2_2") (pintype "passive"))
      (node (ref "VCC-LOGIC") (pin "A") (pinfunction "A_A") (pintype "passive"))
    )
    (net (code "67") (name "Net-(R5-Pad2)") (class "Default")
      (node (ref "R5") (pin "2") (pinfunction "2_2") (pintype "passive"))
      (node (ref "VCC-MOT") (pin "A") (pinfunction "A_A") (pintype "passive"))
    )
    (net (code "68") (name "Net-(R6-Pad1)") (class "Default")
      (node (ref "R6") (pin "1") (pinfunction "1_1") (pintype "passive"))
      (node (ref "T1") (pin "B") (pinfunction "B_B") (pintype "passive"))
    )
    (net (code "69") (name "Net-(R11-Pad1)") (class "Default")
      (node (ref "R11") (pin "1") (pinfunction "1_1") (pintype "passive"))
      (node (ref "T2") (pin "B") (pinfunction "B_B") (pintype "passive"))
    )
    (net (code "70") (name "Net-(R12-Pad1)") (class "Default")
      (node (ref "R12") (pin "1") (pinfunction "1_1") (pintype "passive"))
      (node (ref "T3") (pin "B") (pinfunction "B_B") (pintype "passive"))
    )
    (net (code "71") (name "Net-(R20-Pad1)") (class "Default")
      (node (ref "R20") (pin "1") (pinfunction "1_1") (pintype "passive"))
      (node (ref "T4") (pin "B") (pinfunction "B_B") (pintype "passive"))
    )
    (net (code "72") (name "Net-(RS422C-KL)") (class "Default")
      (node (ref "RS422") (pin "3") (pinfunction "KL_3") (pintype "passive"))
      (node (ref "U6") (pin "5") (pinfunction "Y_5") (pintype "bidirectional"))
    )
    (net (code "73") (name "Net-(RS422D-KL)") (class "Default")
      (node (ref "RS422") (pin "4") (pinfunction "KL_4") (pintype "passive"))
      (node (ref "U6") (pin "6") (pinfunction "Z_6") (pintype "bidirectional"))
    )
    (net (code "74") (name "Net-(RS422E-KL)") (class "Default")
      (node (ref "RS422") (pin "5") (pinfunction "KL_5") (pintype "passive"))
      (node (ref "U6") (pin "7") (pinfunction "B_7") (pintype "bidirectional"))
    )
    (net (code "75") (name "Net-(RS422F-KL)") (class "Default")
      (node (ref "RS422") (pin "6") (pinfunction "KL_6") (pintype "passive"))
      (node (ref "U6") (pin "8") (pinfunction "A_8") (pintype "bidirectional"))
    )
    (net (code "76") (name "Net-(STATUS-PadC)") (class "Default")
      (node (ref "STATUS") (pin "C") (pinfunction "C_C") (pintype "passive"))
      (node (ref "T2") (pin "C") (pinfunction "C_C") (pintype "passive"))
    )
    (net (code "77") (name "Net-(U3-VDD)") (class "Default")
      (node (ref "GPIO") (pin "5") (pinfunction "5_5") (pintype "passive"))
      (node (ref "GPIO") (pin "6") (pinfunction "6_6") (pintype "passive"))
      (node (ref "GPIO-LEVEL") (pin "2") (pinfunction "2_2") (pintype "passive"))
      (node (ref "U3") (pin "16") (pinfunction "VDD_16") (pintype "bidirectional"))
      (node (ref "U4") (pin "1") (pinfunction "VCC_1") (pintype "bidirectional"))
    )
    (net (code "78") (name "OUT1") (class "Default")
      (node (ref "GPIO") (pin "10") (pinfunction "10_10") (pintype "passive"))
      (node (ref "U3") (pin "4") (pinfunction "E_4") (pintype "bidirectional"))
    )
    (net (code "79") (name "OUT2") (class "Default")
      (node (ref "GPIO") (pin "9") (pinfunction "9_9") (pintype "passive"))
      (node (ref "U3") (pin "5") (pinfunction "F_5") (pintype "bidirectional"))
    )
    (net (code "80") (name "OUT3") (class "Default")
      (node (ref "GPIO") (pin "7") (pinfunction "7_7") (pintype "passive"))
      (node (ref "U3") (pin "11") (pinfunction "G_11") (pintype "bidirectional"))
    )
    (net (code "81") (name "OUT4") (class "Default")
      (node (ref "GPIO") (pin "8") (pinfunction "8_8") (pintype "passive"))
      (node (ref "U3") (pin "13") (pinfunction "H_13") (pintype "bidirectional"))
    )
    (net (code "82") (name "OUT_1") (class "Default")
      (node (ref "IC1") (pin "44") (pinfunction "P0[22]/RTS1/TD1_44") (pintype "bidirectional"))
      (node (ref "U3") (pin "3") (pinfunction "A_3") (pintype "bidirectional"))
    )
    (net (code "83") (name "OUT_2") (class "Default")
      (node (ref "IC1") (pin "45") (pinfunction "P0[18]/DCD1/MOSI0/MOSI_45") (pintype "bidirectional"))
      (node (ref "U3") (pin "6") (pinfunction "B_6") (pintype "bidirectional"))
    )
    (net (code "84") (name "OUT_3") (class "Default")
      (node (ref "IC1") (pin "46") (pinfunction "P0[17]/CTS1/MISO0/MISO_46") (pintype "bidirectional"))
      (node (ref "U3") (pin "10") (pinfunction "C_10") (pintype "bidirectional"))
    )
    (net (code "85") (name "OUT_4") (class "Default")
      (node (ref "IC1") (pin "47") (pinfunction "P0[15]/TXD1/SCK0/SCK_47") (pintype "bidirectional"))
      (node (ref "U3") (pin "14") (pinfunction "D_14") (pintype "bidirectional"))
    )
    (net (code "86") (name "PHA") (class "Default")
      (node (ref "IC1") (pin "27") (pinfunction "P1[20]/MCI0/PWM1[2]/SCK0_27") (pintype "bidirectional"))
      (node (ref "U7") (pin "4") (pinfunction "OUTB_4") (pintype "bidirectional"))
    )
    (net (code "87") (name "PHB") (class "Default")
      (node (ref "IC1") (pin "29") (pinfunction "P1[23]/MCI1/PWM1[4]/MISO0_29") (pintype "bidirectional"))
      (node (ref "U7") (pin "6") (pinfunction "OUTC_6") (pintype "bidirectional"))
    )
    (net (code "88") (name "PWM") (class "Default")
      (node (ref "IC2") (pin "8") (pinfunction "PWM_8") (pintype "input"))
      (node (ref "U1") (pin "5") (pinfunction "F_5") (pintype "bidirectional"))
    )
    (net (code "89") (name "PWM-3.3") (class "Default")
      (node (ref "IC1") (pin "31") (pinfunction "P1[25]/MCOA1/MAT1[1]_31") (pintype "bidirectional"))
      (node (ref "U1") (pin "6") (pinfunction "B_6") (pintype "bidirectional"))
    )
    (net (code "90") (name "PWM-FAN") (class "Default")
      (node (ref "IC1") (pin "25") (pinfunction "P1[18]/USB_UP_LED/PWM1[1]/CAP1[0]_25") (pintype "bidirectional"))
      (node (ref "R20") (pin "2") (pinfunction "2_2") (pintype "passive"))
    )
    (net (code "91") (name "RE-RS485") (class "Default")
      (node (ref "IC1") (pin "51") (pinfunction "P2[7]/RD2/RTS1_51") (pintype "bidirectional"))
      (node (ref "IC6") (pin "2") (pinfunction "~{RE}_2") (pintype "input"))
    )
    (net (code "92") (name "RESET") (class "Default")
      (node (ref "IC1") (pin "14") (pinfunction "RESET_14") (pintype "input"))
      (node (ref "JTAG") (pin "4") (pinfunction "4_4") (pintype "bidirectional"))
      (node (ref "R29") (pin "2") (pinfunction "2_2") (pintype "passive"))
    )
    (net (code "93") (name "RS422-RX") (class "Default")
      (node (ref "IC1") (pin "59") (pinfunction "P2[1]/PWM1[2]/RXD1_59") (pintype "bidirectional"))
      (node (ref "U6") (pin "2") (pinfunction "RO_2") (pintype "bidirectional"))
    )
    (net (code "94") (name "RS422-TX") (class "Default")
      (node (ref "IC1") (pin "60") (pinfunction "P2[0]/PWM1[1]/TXD1_60") (pintype "bidirectional"))
      (node (ref "U6") (pin "3") (pinfunction "DI_3") (pintype "bidirectional"))
    )
    (net (code "95") (name "RS485-A") (class "Default")
      (node (ref "B-B-L") (pin "4") (pinfunction "4_4") (pintype "passive"))
      (node (ref "B-B-R") (pin "4") (pinfunction "4_4") (pintype "passive"))
      (node (ref "IC6") (pin "6") (pinfunction "A_6") (pintype "bidirectional"))
      (node (ref "RS422") (pin "1") (pinfunction "KL_1") (pintype "passive"))
    )
    (net (code "96") (name "RS485-B") (class "Default")
      (node (ref "B-B-L") (pin "3") (pinfunction "3_3") (pintype "passive"))
      (node (ref "B-B-R") (pin "3") (pinfunction "3_3") (pintype "passive"))
      (node (ref "IC6") (pin "7") (pinfunction "B_7") (pintype "bidirectional"))
      (node (ref "RS422") (pin "2") (pinfunction "KL_2") (pintype "passive"))
    )
    (net (code "97") (name "RSTOUT") (class "Default")
      (node (ref "IC1") (pin "11") (pinfunction "RSTOUT_11") (pintype "output"))
      (node (ref "JTAG") (pin "2") (pinfunction "2_2") (pintype "bidirectional"))
    )
    (net (code "98") (name "RX-RS485") (class "Default")
      (node (ref "IC1") (pin "38") (pinfunction "P0[1]/TD1/RXD3/SCL1_38") (pintype "bidirectional"))
      (node (ref "IC6") (pin "1") (pinfunction "RO_1") (pintype "output"))
    )
    (net (code "99") (name "SDA_EEPROM") (class "Default")
      (node (ref "IC1") (pin "39") (pinfunction "P0[10]/TXD2/SDA2/MAT3[0]_39") (pintype "bidirectional"))
      (node (ref "IC5") (pin "3") (pinfunction "SDA_3") (pintype "bidirectional"))
      (node (ref "R23") (pin "2") (pinfunction "2_2") (pintype "passive"))
    )
    (net (code "100") (name "SENSE-NTCBOARD") (class "Default")
      (node (ref "C20") (pin "1") (pinfunction "1_1") (pintype "passive"))
      (node (ref "IC1") (pin "6") (pinfunction "P0[26]/AD0[3]/AOUT/RXD3_6") (pintype "bidirectional"))
      (node (ref "R8") (pin "1") (pinfunction "1_1") (pintype "passive"))
    )
    (net (code "101") (name "SENSE-NTCMOT") (class "Default")
      (node (ref "C21") (pin "1") (pinfunction "1_1") (pintype "passive"))
      (node (ref "IC1") (pin "7") (pinfunction "P0[25]/AD0[2]/I2SRX_SDA/TXD3_7") (pintype "bidirectional"))
      (node (ref "R14") (pin "1") (pinfunction "1_1") (pintype "passive"))
    )
    (net (code "102") (name "SENSE-VMOT") (class "Default")
      (node (ref "C22") (pin "1") (pinfunction "1_1") (pintype "passive"))
      (node (ref "IC1") (pin "17") (pinfunction "P1[31]/SCK1/AD0[5]_17") (pintype "bidirectional"))
      (node (ref "R15") (pin "1") (pinfunction "1_1") (pintype "passive"))
    )
    (net (code "103") (name "SPEED-FAN") (class "Default")
      (node (ref "FAN") (pin "1") (pinfunction "S_1") (pintype "passive"))
      (node (ref "IC1") (pin "28") (pinfunction "P1[22]/MCOB0/USB_PWRD/MAT1[0]_28") (pintype "bidirectional"))
      (node (ref "R21") (pin "2") (pinfunction "2_2") (pintype "passive"))
    )
    (net (code "104") (name "TCK") (class "Default")
      (node (ref "IC1") (pin "5") (pinfunction "TCK/SWDCLK_5") (pintype "bidirectional"))
      (node (ref "JTAG") (pin "1") (pinfunction "1_1") (pintype "bidirectional"))
    )
    (net (code "105") (name "TDI") (class "Default")
      (node (ref "IC1") (pin "2") (pinfunction "TDI_2") (pintype "input"))
      (node (ref "JTAG") (pin "7") (pinfunction "7_7") (pintype "bidirectional"))
    )
    (net (code "106") (name "TDO") (class "Default")
      (node (ref "IC1") (pin "1") (pinfunction "TDO/SWO_1") (pintype "output"))
      (node (ref "JTAG") (pin "9") (pinfunction "9_9") (pintype "bidirectional"))
    )
    (net (code "107") (name "TMS") (class "Default")
      (node (ref "IC1") (pin "3") (pinfunction "TMS/SWDIO_3") (pintype "bidirectional"))
      (node (ref "JTAG") (pin "5") (pinfunction "5_5") (pintype "bidirectional"))
    )
    (net (code "108") (name "TRST") (class "Default")
      (node (ref "IC1") (pin "4") (pinfunction "TRST_4") (pintype "bidirectional"))
      (node (ref "JTAG") (pin "3") (pinfunction "3_3") (pintype "bidirectional"))
    )
    (net (code "109") (name "TX-RS485") (class "Default")
      (node (ref "IC1") (pin "37") (pinfunction "P0[0]/RD1/TXD3/SDA1_37") (pintype "bidirectional"))
      (node (ref "IC6") (pin "4") (pinfunction "DI_4") (pintype "input"))
    )
    (net (code "110") (name "VBAT") (class "Default")
      (node (ref "IC1") (pin "16") (pinfunction "VBAT_16") (pintype "power_in"))
    )
    (net (code "111") (name "unconnected-(IC1-P1[28]{slash}MCOA2{slash}PCAP1[0]{slash}MAT0[0]-Pad35)") (class "Default")
      (node (ref "IC1") (pin "35") (pinfunction "P1[28]/MCOA2/PCAP1[0]/MAT0[0]_35") (pintype "bidirectional"))
    )
    (net (code "112") (name "unconnected-(IC1-P1[29]{slash}MCOB2{slash}PCAP1[1]{slash}MAT0[1]-Pad36)") (class "Default")
      (node (ref "IC1") (pin "36") (pinfunction "P1[29]/MCOB2/PCAP1[1]/MAT0[1]_36") (pintype "bidirectional"))
    )
    (net (code "113") (name "unconnected-(IC1-P2[2]{slash}PWM1[3]{slash}CTS1{slash}TRACEDATA[3]-Pad58)") (class "Default")
      (node (ref "IC1") (pin "58") (pinfunction "P2[2]/PWM1[3]/CTS1/TRACEDATA[3]_58") (pintype "bidirectional"))
    )
    (net (code "114") (name "unconnected-(IC1-P2[5]{slash}PWM1[6]{slash}DTR1{slash}TRACEDATA[0]-Pad53)") (class "Default")
      (node (ref "IC1") (pin "53") (pinfunction "P2[5]/PWM1[6]/DTR1/TRACEDATA[0]_53") (pintype "bidirectional"))
    )
    (net (code "115") (name "unconnected-(IC1-P2[8]{slash}TD2{slash}TXD2{slash}ENET_MDC-Pad50)") (class "Default")
      (node (ref "IC1") (pin "50") (pinfunction "P2[8]/TD2/TXD2/ENET_MDC_50") (pintype "bidirectional"))
    )
    (net (code "116") (name "unconnected-(IC1-P4[28]{slash}RX_MCLK{slash}MAT2[0]{slash}TXD3-Pad65)") (class "Default")
      (node (ref "IC1") (pin "65") (pinfunction "P4[28]/RX_MCLK/MAT2[0]/TXD3_65") (pintype "bidirectional"))
    )
    (net (code "117") (name "unconnected-(IC1-RTCX1-Pad13)") (class "Default")
      (node (ref "IC1") (pin "13") (pinfunction "RTCX1_13") (pintype "input"))
    )
    (net (code "118") (name "unconnected-(IC1-RTCX2-Pad15)") (class "Default")
      (node (ref "IC1") (pin "15") (pinfunction "RTCX2_15") (pintype "output"))
    )
    (net (code "119") (name "unconnected-(U1-H-Pad13)") (class "Default")
      (node (ref "U1") (pin "13") (pinfunction "H_13") (pintype "bidirectional"))
    )
    (net (code "120") (name "unconnected-(U3-NC-Pad12)") (class "Default")
      (node (ref "U3") (pin "12") (pinfunction "NC_12") (pintype "bidirectional"))
    )
    (net (code "121") (name "unconnected-(U4-NC-Pad12)") (class "Default")
      (node (ref "U4") (pin "12") (pinfunction "NC_12") (pintype "bidirectional"))
    )
    (net (code "122") (name "unconnected-(U7-NC-Pad13)") (class "Default")
      (node (ref "U7") (pin "13") (pinfunction "NC_13") (pintype "bidirectional"))
    )
    (net (code "123") (name "unconnected-(U7-NC2-Pad16)") (class "Default")
      (node (ref "U7") (pin "16") (pinfunction "NC2_16") (pintype "bidirectional"))
    )
    (net (code "124") (name "unconnected-(U7-OUTD-Pad10)") (class "Default")
      (node (ref "U7") (pin "10") (pinfunction "OUTD_10") (pintype "bidirectional"))
    )
  )
)
